# Switches.net
KiCad netlist of a schematic drawn in EAGLE
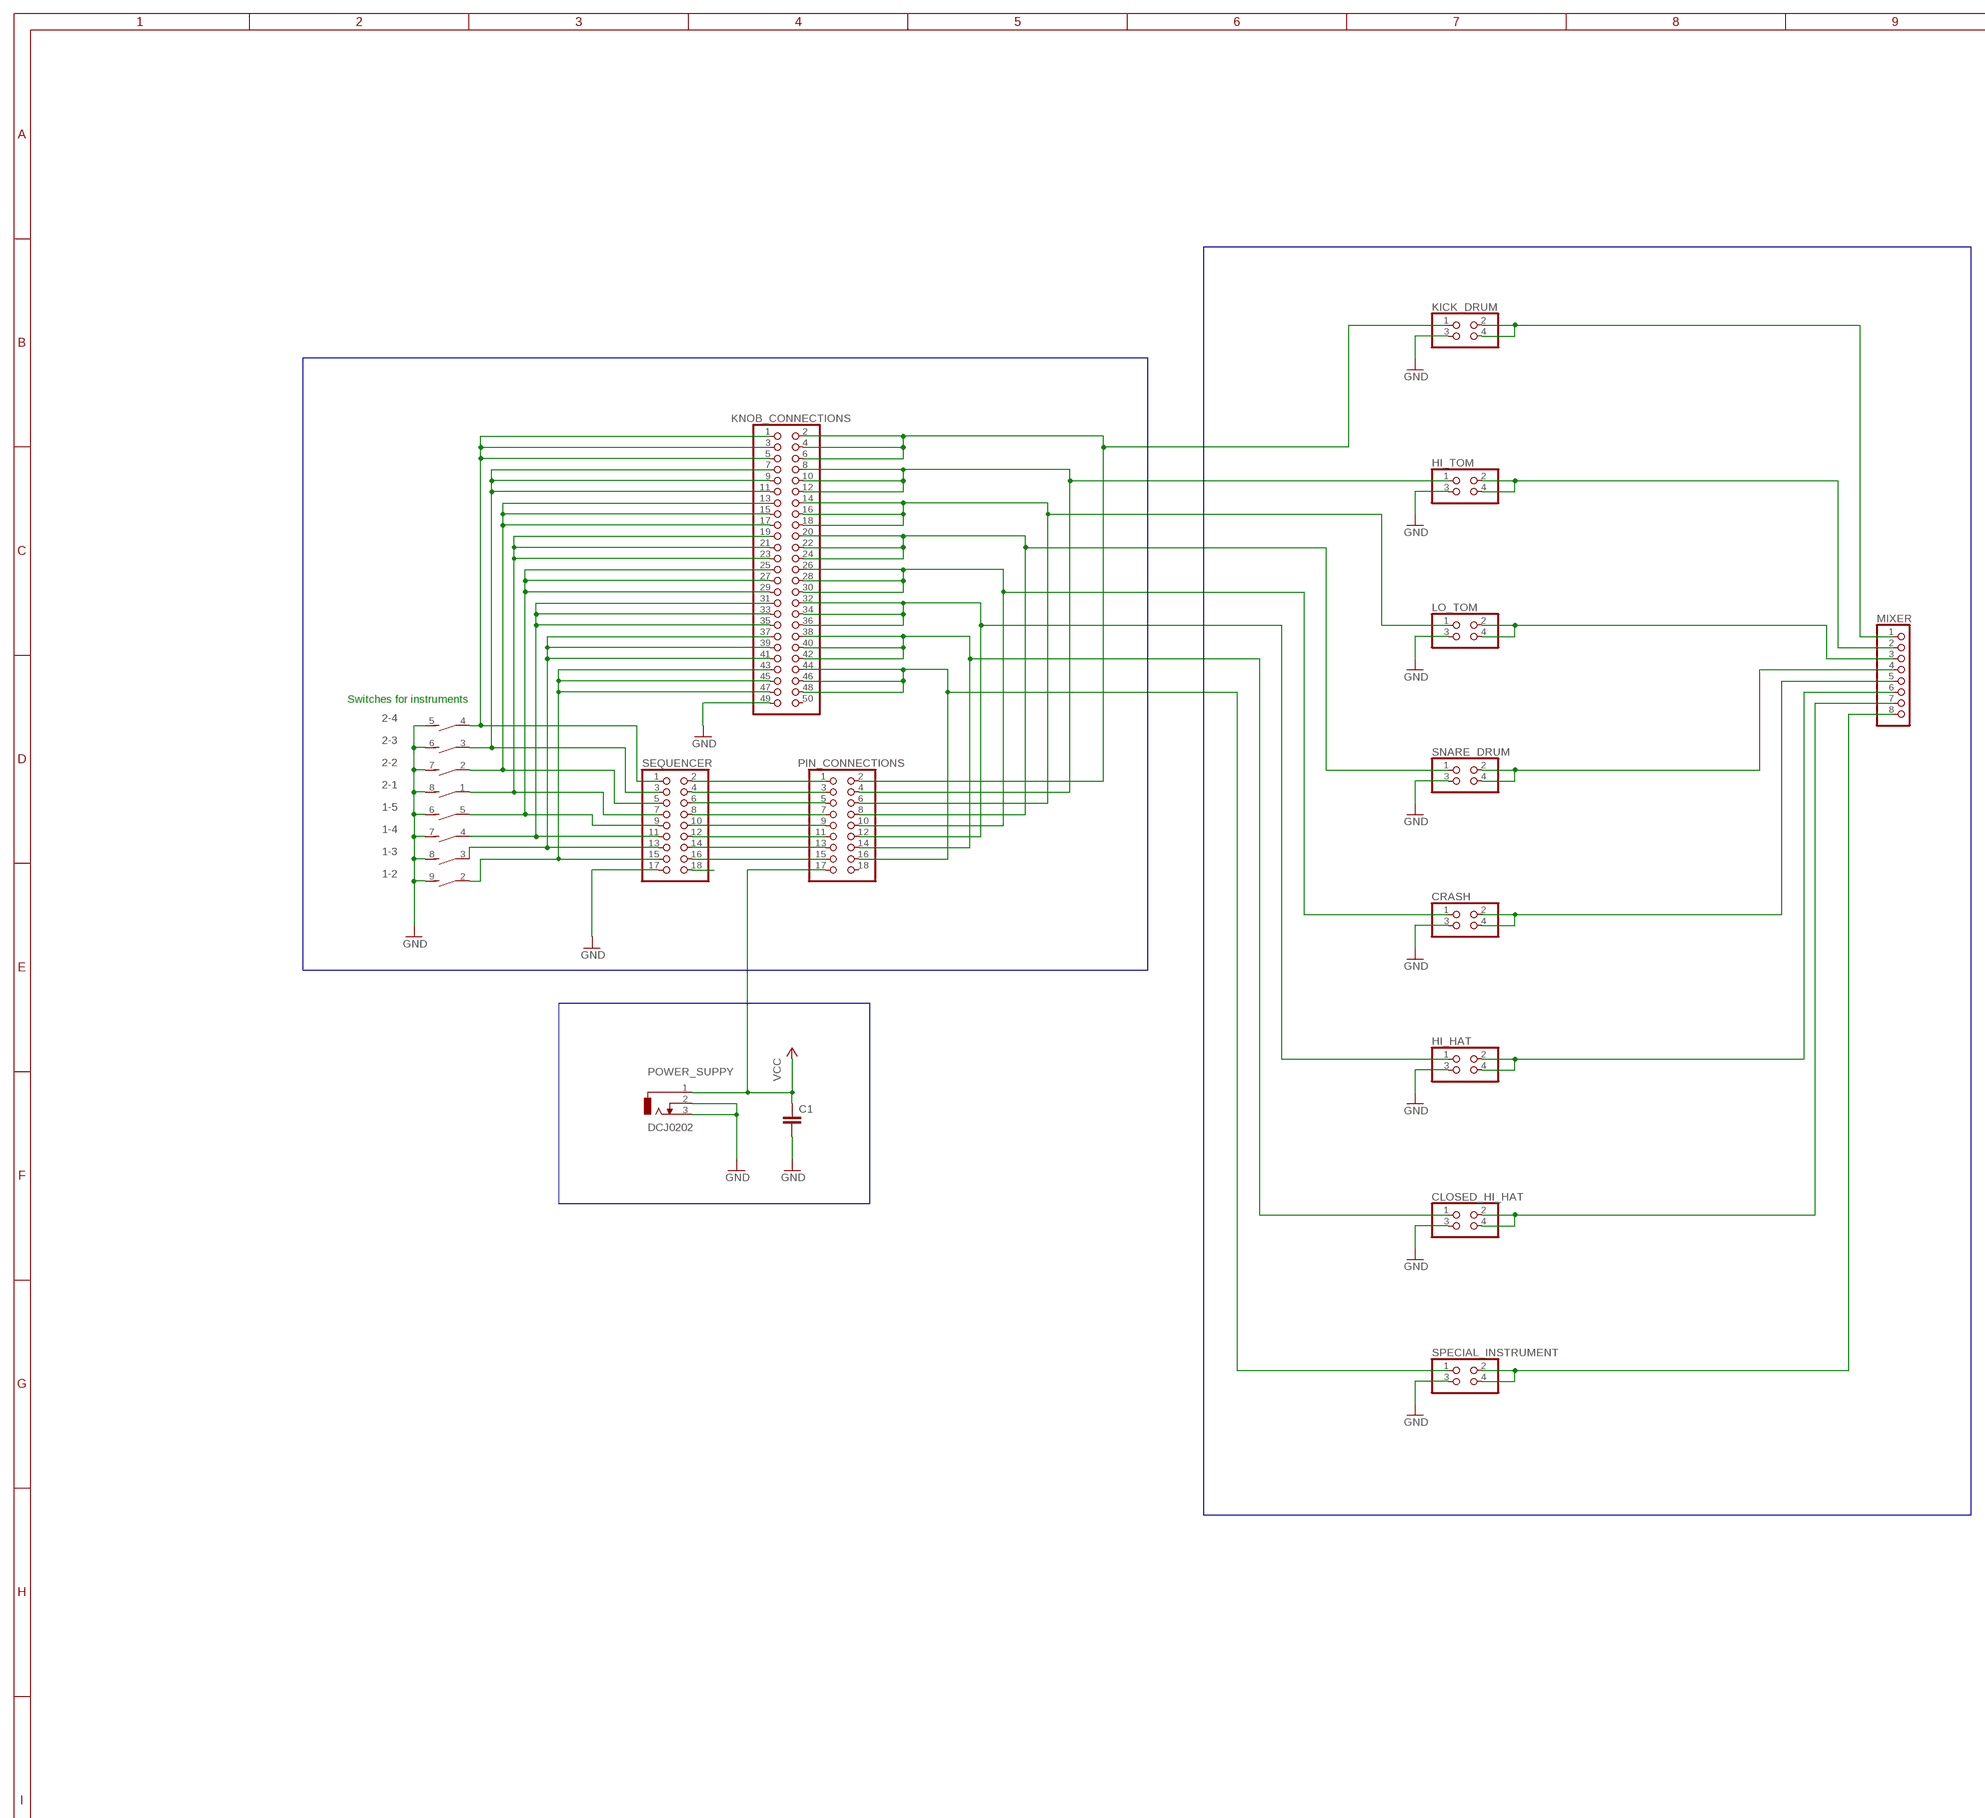
[diagram p0: schematic, sheet 1, part 1 of 2]
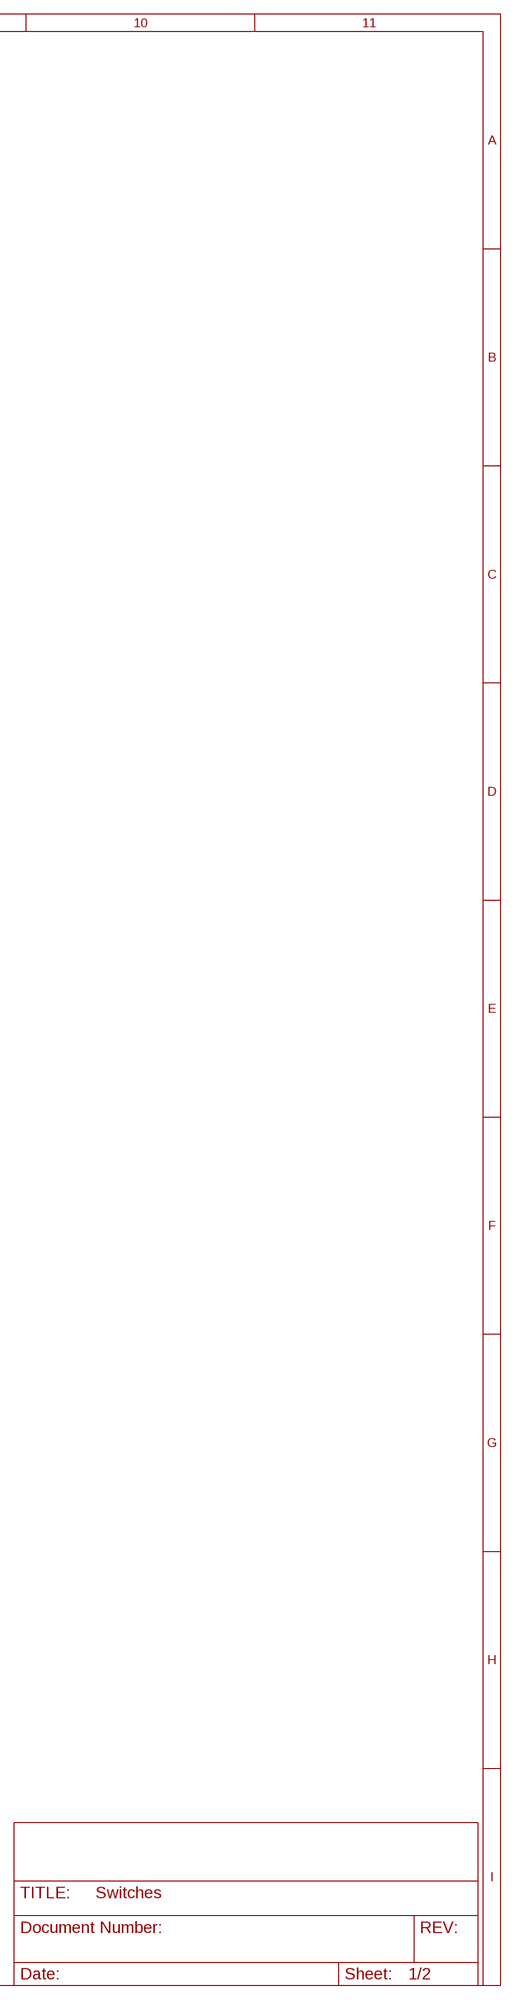
[diagram p1: schematic, sheet 1, part 2 of 2]
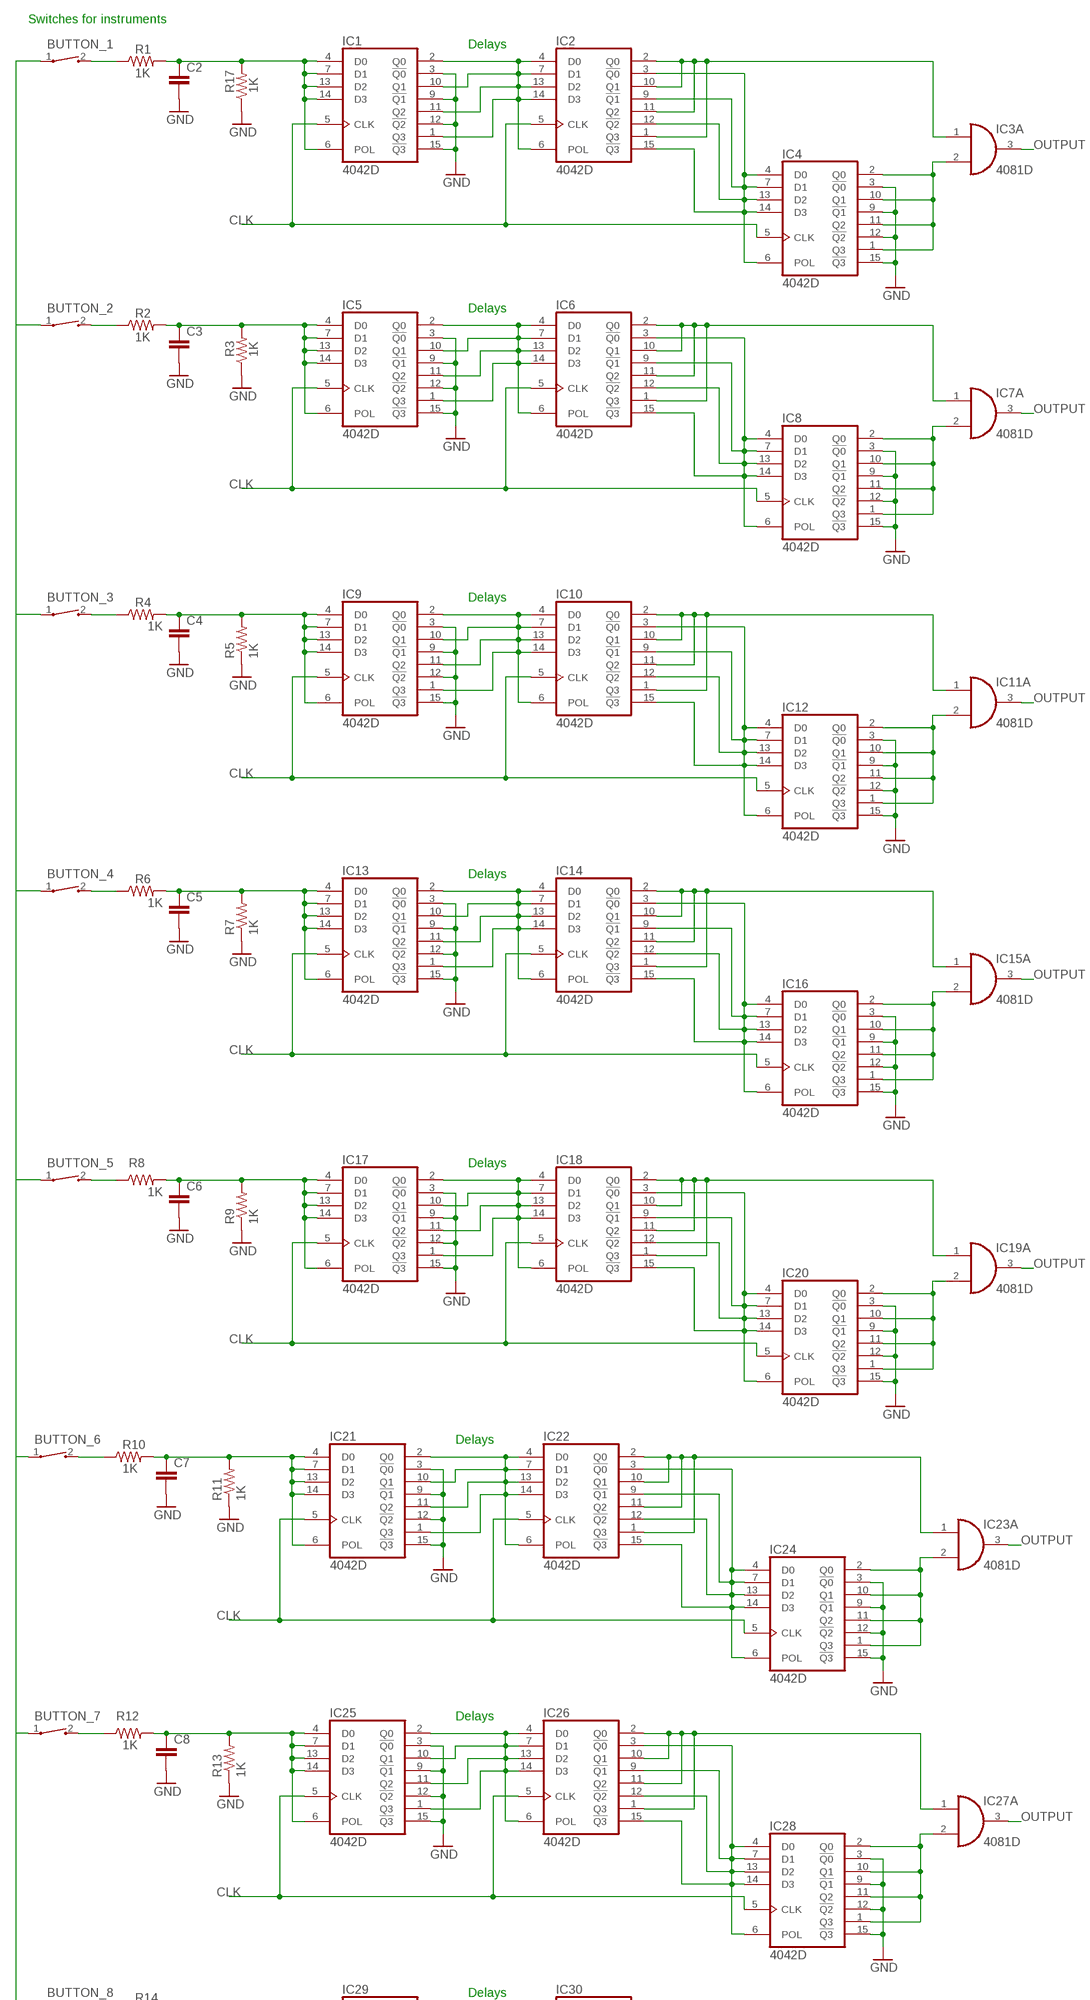
[diagram p2: schematic, sheet 2, part 1 of 3]
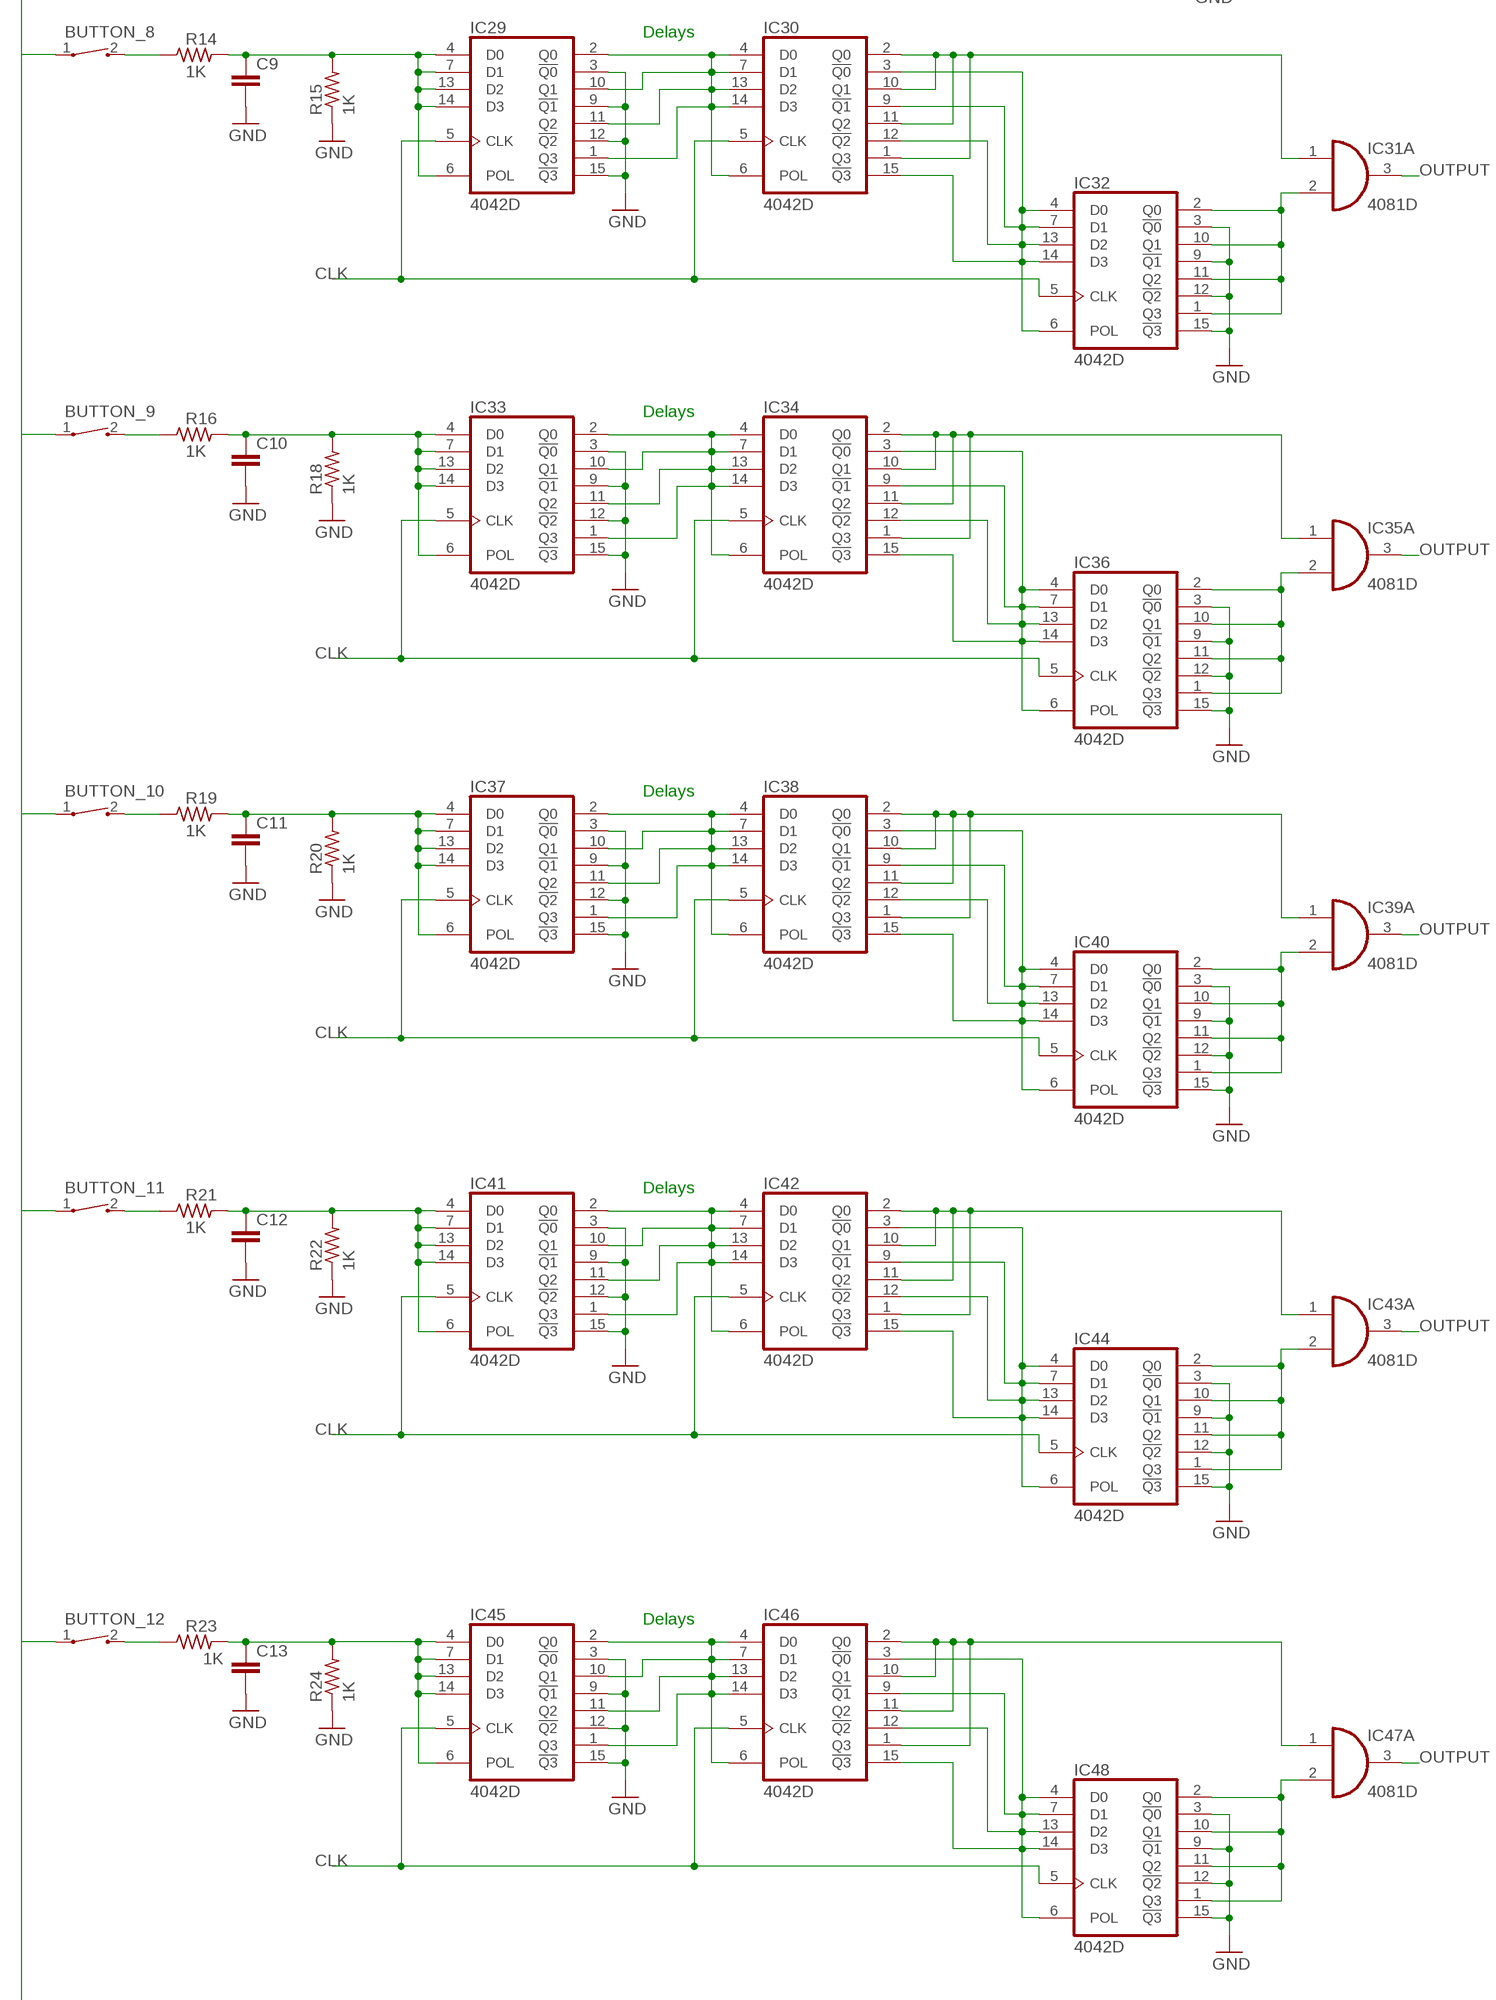
[diagram p3: schematic, sheet 2, part 2 of 3]
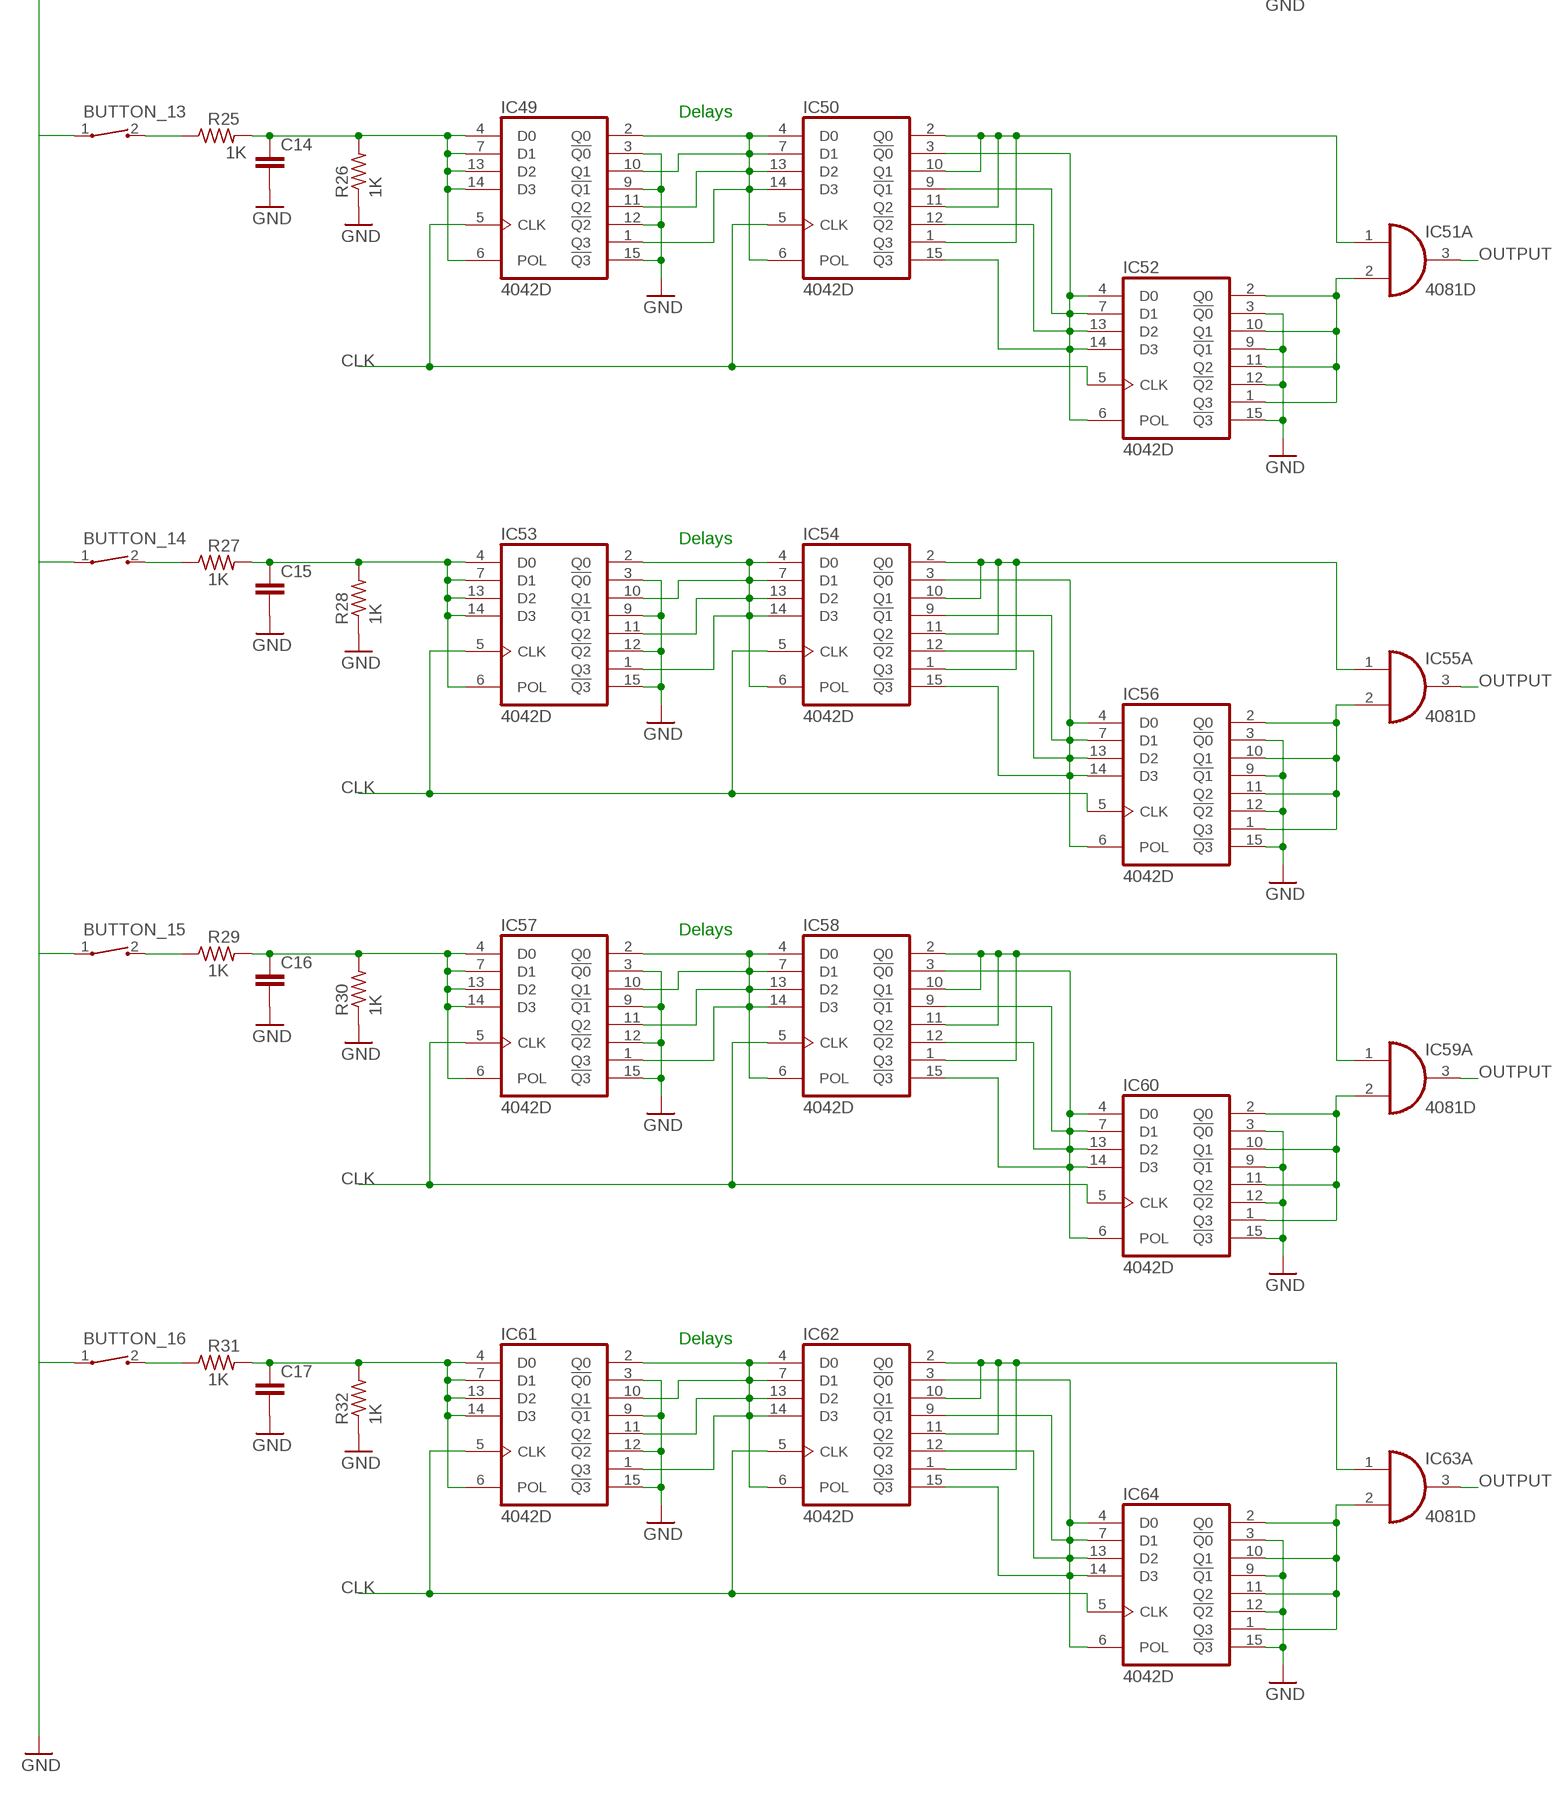
[diagram p4: schematic, sheet 2, part 3 of 3]

(export (version "E")
  (design (tool "Eeschema 10.0.6"))
  (components
    (comp (ref "1")
      (value "DS05E")
      (footprint "eagle-import:DS-05")
      (libsource (lib "eagle-import") (part "DS05E"))
    )
    (comp (ref "2")
      (value "DIP04S")
      (footprint "eagle-import:DIP04S")
      (libsource (lib "eagle-import") (part "DIP04S"))
    )
    (comp (ref "C1")
      (value "C2,5-3")
      (footprint "eagle-import:C2.5-3")
      (libsource (lib "eagle-import") (part "C2,5-3"))
    )
    (comp (ref "CLOSED_HI_HAT")
      (value "PINHD-2X2")
      (footprint "eagle-import:2X02")
      (libsource (lib "eagle-import") (part "PINHD-2X2"))
    )
    (comp (ref "CRASH")
      (value "PINHD-2X2")
      (footprint "eagle-import:2X02")
      (libsource (lib "eagle-import") (part "PINHD-2X2"))
    )
    (comp (ref "HI_HAT")
      (value "PINHD-2X2")
      (footprint "eagle-import:2X02")
      (libsource (lib "eagle-import") (part "PINHD-2X2"))
    )
    (comp (ref "HI_TOM")
      (value "PINHD-2X2")
      (footprint "eagle-import:2X02")
      (libsource (lib "eagle-import") (part "PINHD-2X2"))
    )
    (comp (ref "KICK_DRUM")
      (value "PINHD-2X2")
      (footprint "eagle-import:2X02")
      (libsource (lib "eagle-import") (part "PINHD-2X2"))
    )
    (comp (ref "KNOB_CONNECTIONS")
      (value "PINHD-2X25")
      (footprint "eagle-import:2X25")
      (libsource (lib "eagle-import") (part "PINHD-2X25"))
    )
    (comp (ref "LO_TOM")
      (value "PINHD-2X2")
      (footprint "eagle-import:2X02")
      (libsource (lib "eagle-import") (part "PINHD-2X2"))
    )
    (comp (ref "MIXER")
      (value "PINHD-1X8")
      (footprint "eagle-import:1X08")
      (libsource (lib "eagle-import") (part "PINHD-1X8"))
    )
    (comp (ref "PIN_CONNECTIONS")
      (value "PINHD-2X9")
      (footprint "eagle-import:2X09")
      (libsource (lib "eagle-import") (part "PINHD-2X9"))
    )
    (comp (ref "POWER_SUPPY")
      (value "DCJ0202")
      (footprint "eagle-import:DCJ0202")
      (libsource (lib "eagle-import") (part "DCJ0202"))
    )
    (comp (ref "SEQUENCER")
      (value "PINHD-2X9")
      (footprint "eagle-import:2X09")
      (libsource (lib "eagle-import") (part "PINHD-2X9"))
    )
    (comp (ref "SNARE_DRUM")
      (value "PINHD-2X2")
      (footprint "eagle-import:2X02")
      (libsource (lib "eagle-import") (part "PINHD-2X2"))
    )
    (comp (ref "SPECIAL_INSTRUMENT")
      (value "PINHD-2X2")
      (footprint "eagle-import:2X02")
      (libsource (lib "eagle-import") (part "PINHD-2X2"))
    )
    (comp (ref "BUTTON_1")
      (value "CT10-XXXX-A2")
      (footprint "eagle-import:CT10-XXXX-A2")
      (libsource (lib "eagle-import") (part "CT10-XXXX-A2"))
    )
    (comp (ref "BUTTON_2")
      (value "CT10-XXXX-A2")
      (footprint "eagle-import:CT10-XXXX-A2")
      (libsource (lib "eagle-import") (part "CT10-XXXX-A2"))
    )
    (comp (ref "BUTTON_3")
      (value "CT10-XXXX-A2")
      (footprint "eagle-import:CT10-XXXX-A2")
      (libsource (lib "eagle-import") (part "CT10-XXXX-A2"))
    )
    (comp (ref "BUTTON_4")
      (value "CT10-XXXX-A2")
      (footprint "eagle-import:CT10-XXXX-A2")
      (libsource (lib "eagle-import") (part "CT10-XXXX-A2"))
    )
    (comp (ref "BUTTON_5")
      (value "CT10-XXXX-A2")
      (footprint "eagle-import:CT10-XXXX-A2")
      (libsource (lib "eagle-import") (part "CT10-XXXX-A2"))
    )
    (comp (ref "BUTTON_6")
      (value "CT10-XXXX-A2")
      (footprint "eagle-import:CT10-XXXX-A2")
      (libsource (lib "eagle-import") (part "CT10-XXXX-A2"))
    )
    (comp (ref "BUTTON_7")
      (value "CT10-XXXX-A2")
      (footprint "eagle-import:CT10-XXXX-A2")
      (libsource (lib "eagle-import") (part "CT10-XXXX-A2"))
    )
    (comp (ref "BUTTON_8")
      (value "CT10-XXXX-A2")
      (footprint "eagle-import:CT10-XXXX-A2")
      (libsource (lib "eagle-import") (part "CT10-XXXX-A2"))
    )
    (comp (ref "BUTTON_9")
      (value "CT10-XXXX-A2")
      (footprint "eagle-import:CT10-XXXX-A2")
      (libsource (lib "eagle-import") (part "CT10-XXXX-A2"))
    )
    (comp (ref "BUTTON_10")
      (value "CT10-XXXX-A2")
      (footprint "eagle-import:CT10-XXXX-A2")
      (libsource (lib "eagle-import") (part "CT10-XXXX-A2"))
    )
    (comp (ref "BUTTON_11")
      (value "CT10-XXXX-A2")
      (footprint "eagle-import:CT10-XXXX-A2")
      (libsource (lib "eagle-import") (part "CT10-XXXX-A2"))
    )
    (comp (ref "BUTTON_12")
      (value "CT10-XXXX-A2")
      (footprint "eagle-import:CT10-XXXX-A2")
      (libsource (lib "eagle-import") (part "CT10-XXXX-A2"))
    )
    (comp (ref "BUTTON_13")
      (value "CT10-XXXX-A2")
      (footprint "eagle-import:CT10-XXXX-A2")
      (libsource (lib "eagle-import") (part "CT10-XXXX-A2"))
    )
    (comp (ref "BUTTON_14")
      (value "CT10-XXXX-A2")
      (footprint "eagle-import:CT10-XXXX-A2")
      (libsource (lib "eagle-import") (part "CT10-XXXX-A2"))
    )
    (comp (ref "BUTTON_15")
      (value "CT10-XXXX-A2")
      (footprint "eagle-import:CT10-XXXX-A2")
      (libsource (lib "eagle-import") (part "CT10-XXXX-A2"))
    )
    (comp (ref "BUTTON_16")
      (value "CT10-XXXX-A2")
      (footprint "eagle-import:CT10-XXXX-A2")
      (libsource (lib "eagle-import") (part "CT10-XXXX-A2"))
    )
    (comp (ref "C2")
      (value "C5/3")
      (footprint "eagle-import:C5B3")
      (libsource (lib "eagle-import") (part "C5/3"))
    )
    (comp (ref "C3")
      (value "C5/3")
      (footprint "eagle-import:C5B3")
      (libsource (lib "eagle-import") (part "C5/3"))
    )
    (comp (ref "C4")
      (value "C5/3")
      (footprint "eagle-import:C5B3")
      (libsource (lib "eagle-import") (part "C5/3"))
    )
    (comp (ref "C5")
      (value "C5/3")
      (footprint "eagle-import:C5B3")
      (libsource (lib "eagle-import") (part "C5/3"))
    )
    (comp (ref "C6")
      (value "C5/3")
      (footprint "eagle-import:C5B3")
      (libsource (lib "eagle-import") (part "C5/3"))
    )
    (comp (ref "C7")
      (value "C5/3")
      (footprint "eagle-import:C5B3")
      (libsource (lib "eagle-import") (part "C5/3"))
    )
    (comp (ref "C8")
      (value "C5/3")
      (footprint "eagle-import:C5B3")
      (libsource (lib "eagle-import") (part "C5/3"))
    )
    (comp (ref "C9")
      (value "C5/3")
      (footprint "eagle-import:C5B3")
      (libsource (lib "eagle-import") (part "C5/3"))
    )
    (comp (ref "C10")
      (value "C5/3")
      (footprint "eagle-import:C5B3")
      (libsource (lib "eagle-import") (part "C5/3"))
    )
    (comp (ref "C11")
      (value "C5/3")
      (footprint "eagle-import:C5B3")
      (libsource (lib "eagle-import") (part "C5/3"))
    )
    (comp (ref "C12")
      (value "C5/3")
      (footprint "eagle-import:C5B3")
      (libsource (lib "eagle-import") (part "C5/3"))
    )
    (comp (ref "C13")
      (value "C5/3")
      (footprint "eagle-import:C5B3")
      (libsource (lib "eagle-import") (part "C5/3"))
    )
    (comp (ref "C14")
      (value "C5/3")
      (footprint "eagle-import:C5B3")
      (libsource (lib "eagle-import") (part "C5/3"))
    )
    (comp (ref "C15")
      (value "C5/3")
      (footprint "eagle-import:C5B3")
      (libsource (lib "eagle-import") (part "C5/3"))
    )
    (comp (ref "C16")
      (value "C5/3")
      (footprint "eagle-import:C5B3")
      (libsource (lib "eagle-import") (part "C5/3"))
    )
    (comp (ref "C17")
      (value "C5/3")
      (footprint "eagle-import:C5B3")
      (libsource (lib "eagle-import") (part "C5/3"))
    )
    (comp (ref "IC1")
      (value "4042D")
      (footprint "eagle-import:SO16")
      (libsource (lib "eagle-import") (part "4042D"))
    )
    (comp (ref "IC2")
      (value "4042D")
      (footprint "eagle-import:SO16")
      (libsource (lib "eagle-import") (part "4042D"))
    )
    (comp (ref "IC3")
      (value "4081D")
      (footprint "eagle-import:SO14")
      (libsource (lib "eagle-import") (part "4081D"))
    )
    (comp (ref "IC4")
      (value "4042D")
      (footprint "eagle-import:SO16")
      (libsource (lib "eagle-import") (part "4042D"))
    )
    (comp (ref "IC5")
      (value "4042D")
      (footprint "eagle-import:SO16")
      (libsource (lib "eagle-import") (part "4042D"))
    )
    (comp (ref "IC6")
      (value "4042D")
      (footprint "eagle-import:SO16")
      (libsource (lib "eagle-import") (part "4042D"))
    )
    (comp (ref "IC7")
      (value "4081D")
      (footprint "eagle-import:SO14")
      (libsource (lib "eagle-import") (part "4081D"))
    )
    (comp (ref "IC8")
      (value "4042D")
      (footprint "eagle-import:SO16")
      (libsource (lib "eagle-import") (part "4042D"))
    )
    (comp (ref "IC9")
      (value "4042D")
      (footprint "eagle-import:SO16")
      (libsource (lib "eagle-import") (part "4042D"))
    )
    (comp (ref "IC10")
      (value "4042D")
      (footprint "eagle-import:SO16")
      (libsource (lib "eagle-import") (part "4042D"))
    )
    (comp (ref "IC11")
      (value "4081D")
      (footprint "eagle-import:SO14")
      (libsource (lib "eagle-import") (part "4081D"))
    )
    (comp (ref "IC12")
      (value "4042D")
      (footprint "eagle-import:SO16")
      (libsource (lib "eagle-import") (part "4042D"))
    )
    (comp (ref "IC13")
      (value "4042D")
      (footprint "eagle-import:SO16")
      (libsource (lib "eagle-import") (part "4042D"))
    )
    (comp (ref "IC14")
      (value "4042D")
      (footprint "eagle-import:SO16")
      (libsource (lib "eagle-import") (part "4042D"))
    )
    (comp (ref "IC15")
      (value "4081D")
      (footprint "eagle-import:SO14")
      (libsource (lib "eagle-import") (part "4081D"))
    )
    (comp (ref "IC16")
      (value "4042D")
      (footprint "eagle-import:SO16")
      (libsource (lib "eagle-import") (part "4042D"))
    )
    (comp (ref "IC17")
      (value "4042D")
      (footprint "eagle-import:SO16")
      (libsource (lib "eagle-import") (part "4042D"))
    )
    (comp (ref "IC18")
      (value "4042D")
      (footprint "eagle-import:SO16")
      (libsource (lib "eagle-import") (part "4042D"))
    )
    (comp (ref "IC19")
      (value "4081D")
      (footprint "eagle-import:SO14")
      (libsource (lib "eagle-import") (part "4081D"))
    )
    (comp (ref "IC20")
      (value "4042D")
      (footprint "eagle-import:SO16")
      (libsource (lib "eagle-import") (part "4042D"))
    )
    (comp (ref "IC21")
      (value "4042D")
      (footprint "eagle-import:SO16")
      (libsource (lib "eagle-import") (part "4042D"))
    )
    (comp (ref "IC22")
      (value "4042D")
      (footprint "eagle-import:SO16")
      (libsource (lib "eagle-import") (part "4042D"))
    )
    (comp (ref "IC23")
      (value "4081D")
      (footprint "eagle-import:SO14")
      (libsource (lib "eagle-import") (part "4081D"))
    )
    (comp (ref "IC24")
      (value "4042D")
      (footprint "eagle-import:SO16")
      (libsource (lib "eagle-import") (part "4042D"))
    )
    (comp (ref "IC25")
      (value "4042D")
      (footprint "eagle-import:SO16")
      (libsource (lib "eagle-import") (part "4042D"))
    )
    (comp (ref "IC26")
      (value "4042D")
      (footprint "eagle-import:SO16")
      (libsource (lib "eagle-import") (part "4042D"))
    )
    (comp (ref "IC27")
      (value "4081D")
      (footprint "eagle-import:SO14")
      (libsource (lib "eagle-import") (part "4081D"))
    )
    (comp (ref "IC28")
      (value "4042D")
      (footprint "eagle-import:SO16")
      (libsource (lib "eagle-import") (part "4042D"))
    )
    (comp (ref "IC29")
      (value "4042D")
      (footprint "eagle-import:SO16")
      (libsource (lib "eagle-import") (part "4042D"))
    )
    (comp (ref "IC30")
      (value "4042D")
      (footprint "eagle-import:SO16")
      (libsource (lib "eagle-import") (part "4042D"))
    )
    (comp (ref "IC31")
      (value "4081D")
      (footprint "eagle-import:SO14")
      (libsource (lib "eagle-import") (part "4081D"))
    )
    (comp (ref "IC32")
      (value "4042D")
      (footprint "eagle-import:SO16")
      (libsource (lib "eagle-import") (part "4042D"))
    )
    (comp (ref "IC33")
      (value "4042D")
      (footprint "eagle-import:SO16")
      (libsource (lib "eagle-import") (part "4042D"))
    )
    (comp (ref "IC34")
      (value "4042D")
      (footprint "eagle-import:SO16")
      (libsource (lib "eagle-import") (part "4042D"))
    )
    (comp (ref "IC35")
      (value "4081D")
      (footprint "eagle-import:SO14")
      (libsource (lib "eagle-import") (part "4081D"))
    )
    (comp (ref "IC36")
      (value "4042D")
      (footprint "eagle-import:SO16")
      (libsource (lib "eagle-import") (part "4042D"))
    )
    (comp (ref "IC37")
      (value "4042D")
      (footprint "eagle-import:SO16")
      (libsource (lib "eagle-import") (part "4042D"))
    )
    (comp (ref "IC38")
      (value "4042D")
      (footprint "eagle-import:SO16")
      (libsource (lib "eagle-import") (part "4042D"))
    )
    (comp (ref "IC39")
      (value "4081D")
      (footprint "eagle-import:SO14")
      (libsource (lib "eagle-import") (part "4081D"))
    )
    (comp (ref "IC40")
      (value "4042D")
      (footprint "eagle-import:SO16")
      (libsource (lib "eagle-import") (part "4042D"))
    )
    (comp (ref "IC41")
      (value "4042D")
      (footprint "eagle-import:SO16")
      (libsource (lib "eagle-import") (part "4042D"))
    )
    (comp (ref "IC42")
      (value "4042D")
      (footprint "eagle-import:SO16")
      (libsource (lib "eagle-import") (part "4042D"))
    )
    (comp (ref "IC43")
      (value "4081D")
      (footprint "eagle-import:SO14")
      (libsource (lib "eagle-import") (part "4081D"))
    )
    (comp (ref "IC44")
      (value "4042D")
      (footprint "eagle-import:SO16")
      (libsource (lib "eagle-import") (part "4042D"))
    )
    (comp (ref "IC45")
      (value "4042D")
      (footprint "eagle-import:SO16")
      (libsource (lib "eagle-import") (part "4042D"))
    )
    (comp (ref "IC46")
      (value "4042D")
      (footprint "eagle-import:SO16")
      (libsource (lib "eagle-import") (part "4042D"))
    )
    (comp (ref "IC47")
      (value "4081D")
      (footprint "eagle-import:SO14")
      (libsource (lib "eagle-import") (part "4081D"))
    )
    (comp (ref "IC48")
      (value "4042D")
      (footprint "eagle-import:SO16")
      (libsource (lib "eagle-import") (part "4042D"))
    )
    (comp (ref "IC49")
      (value "4042D")
      (footprint "eagle-import:SO16")
      (libsource (lib "eagle-import") (part "4042D"))
    )
    (comp (ref "IC50")
      (value "4042D")
      (footprint "eagle-import:SO16")
      (libsource (lib "eagle-import") (part "4042D"))
    )
    (comp (ref "IC51")
      (value "4081D")
      (footprint "eagle-import:SO14")
      (libsource (lib "eagle-import") (part "4081D"))
    )
    (comp (ref "IC52")
      (value "4042D")
      (footprint "eagle-import:SO16")
      (libsource (lib "eagle-import") (part "4042D"))
    )
    (comp (ref "IC53")
      (value "4042D")
      (footprint "eagle-import:SO16")
      (libsource (lib "eagle-import") (part "4042D"))
    )
    (comp (ref "IC54")
      (value "4042D")
      (footprint "eagle-import:SO16")
      (libsource (lib "eagle-import") (part "4042D"))
    )
    (comp (ref "IC55")
      (value "4081D")
      (footprint "eagle-import:SO14")
      (libsource (lib "eagle-import") (part "4081D"))
    )
    (comp (ref "IC56")
      (value "4042D")
      (footprint "eagle-import:SO16")
      (libsource (lib "eagle-import") (part "4042D"))
    )
    (comp (ref "IC57")
      (value "4042D")
      (footprint "eagle-import:SO16")
      (libsource (lib "eagle-import") (part "4042D"))
    )
    (comp (ref "IC58")
      (value "4042D")
      (footprint "eagle-import:SO16")
      (libsource (lib "eagle-import") (part "4042D"))
    )
    (comp (ref "IC59")
      (value "4081D")
      (footprint "eagle-import:SO14")
      (libsource (lib "eagle-import") (part "4081D"))
    )
    (comp (ref "IC60")
      (value "4042D")
      (footprint "eagle-import:SO16")
      (libsource (lib "eagle-import") (part "4042D"))
    )
    (comp (ref "IC61")
      (value "4042D")
      (footprint "eagle-import:SO16")
      (libsource (lib "eagle-import") (part "4042D"))
    )
    (comp (ref "IC62")
      (value "4042D")
      (footprint "eagle-import:SO16")
      (libsource (lib "eagle-import") (part "4042D"))
    )
    (comp (ref "IC63")
      (value "4081D")
      (footprint "eagle-import:SO14")
      (libsource (lib "eagle-import") (part "4081D"))
    )
    (comp (ref "IC64")
      (value "4042D")
      (footprint "eagle-import:SO16")
      (libsource (lib "eagle-import") (part "4042D"))
    )
    (comp (ref "R1")
      (value "1K")
      (footprint "eagle-import:0204_7")
      (libsource (lib "eagle-import") (part "R-US_0204/7"))
    )
    (comp (ref "R2")
      (value "1K")
      (footprint "eagle-import:0204_7")
      (libsource (lib "eagle-import") (part "R-US_0204/7"))
    )
    (comp (ref "R3")
      (value "1K")
      (footprint "eagle-import:0204_7")
      (libsource (lib "eagle-import") (part "R-US_0204/7"))
    )
    (comp (ref "R4")
      (value "1K")
      (footprint "eagle-import:0204_7")
      (libsource (lib "eagle-import") (part "R-US_0204/7"))
    )
    (comp (ref "R5")
      (value "1K")
      (footprint "eagle-import:0204_7")
      (libsource (lib "eagle-import") (part "R-US_0204/7"))
    )
    (comp (ref "R6")
      (value "1K")
      (footprint "eagle-import:0204_7")
      (libsource (lib "eagle-import") (part "R-US_0204/7"))
    )
    (comp (ref "R7")
      (value "1K")
      (footprint "eagle-import:0204_7")
      (libsource (lib "eagle-import") (part "R-US_0204/7"))
    )
    (comp (ref "R8")
      (value "1K")
      (footprint "eagle-import:0204_7")
      (libsource (lib "eagle-import") (part "R-US_0204/7"))
    )
    (comp (ref "R9")
      (value "1K")
      (footprint "eagle-import:0204_7")
      (libsource (lib "eagle-import") (part "R-US_0204/7"))
    )
    (comp (ref "R10")
      (value "1K")
      (footprint "eagle-import:0204_7")
      (libsource (lib "eagle-import") (part "R-US_0204/7"))
    )
    (comp (ref "R11")
      (value "1K")
      (footprint "eagle-import:0204_7")
      (libsource (lib "eagle-import") (part "R-US_0204/7"))
    )
    (comp (ref "R12")
      (value "1K")
      (footprint "eagle-import:0204_7")
      (libsource (lib "eagle-import") (part "R-US_0204/7"))
    )
    (comp (ref "R13")
      (value "1K")
      (footprint "eagle-import:0204_7")
      (libsource (lib "eagle-import") (part "R-US_0204/7"))
    )
    (comp (ref "R14")
      (value "1K")
      (footprint "eagle-import:0204_7")
      (libsource (lib "eagle-import") (part "R-US_0204/7"))
    )
    (comp (ref "R15")
      (value "1K")
      (footprint "eagle-import:0204_7")
      (libsource (lib "eagle-import") (part "R-US_0204/7"))
    )
    (comp (ref "R16")
      (value "1K")
      (footprint "eagle-import:0204_7")
      (libsource (lib "eagle-import") (part "R-US_0204/7"))
    )
    (comp (ref "R17")
      (value "1K")
      (footprint "eagle-import:0204_7")
      (libsource (lib "eagle-import") (part "R-US_0204/7"))
    )
    (comp (ref "R18")
      (value "1K")
      (footprint "eagle-import:0204_7")
      (libsource (lib "eagle-import") (part "R-US_0204/7"))
    )
    (comp (ref "R19")
      (value "1K")
      (footprint "eagle-import:0204_7")
      (libsource (lib "eagle-import") (part "R-US_0204/7"))
    )
    (comp (ref "R20")
      (value "1K")
      (footprint "eagle-import:0204_7")
      (libsource (lib "eagle-import") (part "R-US_0204/7"))
    )
    (comp (ref "R21")
      (value "1K")
      (footprint "eagle-import:0204_7")
      (libsource (lib "eagle-import") (part "R-US_0204/7"))
    )
    (comp (ref "R22")
      (value "1K")
      (footprint "eagle-import:0204_7")
      (libsource (lib "eagle-import") (part "R-US_0204/7"))
    )
    (comp (ref "R23")
      (value "1K")
      (footprint "eagle-import:0204_7")
      (libsource (lib "eagle-import") (part "R-US_0204/7"))
    )
    (comp (ref "R24")
      (value "1K")
      (footprint "eagle-import:0204_7")
      (libsource (lib "eagle-import") (part "R-US_0204/7"))
    )
    (comp (ref "R25")
      (value "1K")
      (footprint "eagle-import:0204_7")
      (libsource (lib "eagle-import") (part "R-US_0204/7"))
    )
    (comp (ref "R26")
      (value "1K")
      (footprint "eagle-import:0204_7")
      (libsource (lib "eagle-import") (part "R-US_0204/7"))
    )
    (comp (ref "R27")
      (value "1K")
      (footprint "eagle-import:0204_7")
      (libsource (lib "eagle-import") (part "R-US_0204/7"))
    )
    (comp (ref "R28")
      (value "1K")
      (footprint "eagle-import:0204_7")
      (libsource (lib "eagle-import") (part "R-US_0204/7"))
    )
    (comp (ref "R29")
      (value "1K")
      (footprint "eagle-import:0204_7")
      (libsource (lib "eagle-import") (part "R-US_0204/7"))
    )
    (comp (ref "R30")
      (value "1K")
      (footprint "eagle-import:0204_7")
      (libsource (lib "eagle-import") (part "R-US_0204/7"))
    )
    (comp (ref "R31")
      (value "1K")
      (footprint "eagle-import:0204_7")
      (libsource (lib "eagle-import") (part "R-US_0204/7"))
    )
    (comp (ref "R32")
      (value "1K")
      (footprint "eagle-import:0204_7")
      (libsource (lib "eagle-import") (part "R-US_0204/7"))
    )
  )
  (nets
    (net (code "1") (name "CLK") (class "Default")
      (node (ref "IC1") (pin "5") (pinfunction "CLK_5") (pintype "input"))
      (node (ref "IC10") (pin "5") (pinfunction "CLK_5") (pintype "input"))
      (node (ref "IC12") (pin "5") (pinfunction "CLK_5") (pintype "input"))
      (node (ref "IC13") (pin "5") (pinfunction "CLK_5") (pintype "input"))
      (node (ref "IC14") (pin "5") (pinfunction "CLK_5") (pintype "input"))
      (node (ref "IC16") (pin "5") (pinfunction "CLK_5") (pintype "input"))
      (node (ref "IC17") (pin "5") (pinfunction "CLK_5") (pintype "input"))
      (node (ref "IC18") (pin "5") (pinfunction "CLK_5") (pintype "input"))
      (node (ref "IC2") (pin "5") (pinfunction "CLK_5") (pintype "input"))
      (node (ref "IC20") (pin "5") (pinfunction "CLK_5") (pintype "input"))
      (node (ref "IC21") (pin "5") (pinfunction "CLK_5") (pintype "input"))
      (node (ref "IC22") (pin "5") (pinfunction "CLK_5") (pintype "input"))
      (node (ref "IC24") (pin "5") (pinfunction "CLK_5") (pintype "input"))
      (node (ref "IC25") (pin "5") (pinfunction "CLK_5") (pintype "input"))
      (node (ref "IC26") (pin "5") (pinfunction "CLK_5") (pintype "input"))
      (node (ref "IC28") (pin "5") (pinfunction "CLK_5") (pintype "input"))
      (node (ref "IC29") (pin "5") (pinfunction "CLK_5") (pintype "input"))
      (node (ref "IC30") (pin "5") (pinfunction "CLK_5") (pintype "input"))
      (node (ref "IC32") (pin "5") (pinfunction "CLK_5") (pintype "input"))
      (node (ref "IC33") (pin "5") (pinfunction "CLK_5") (pintype "input"))
      (node (ref "IC34") (pin "5") (pinfunction "CLK_5") (pintype "input"))
      (node (ref "IC36") (pin "5") (pinfunction "CLK_5") (pintype "input"))
      (node (ref "IC37") (pin "5") (pinfunction "CLK_5") (pintype "input"))
      (node (ref "IC38") (pin "5") (pinfunction "CLK_5") (pintype "input"))
      (node (ref "IC4") (pin "5") (pinfunction "CLK_5") (pintype "input"))
      (node (ref "IC40") (pin "5") (pinfunction "CLK_5") (pintype "input"))
      (node (ref "IC41") (pin "5") (pinfunction "CLK_5") (pintype "input"))
      (node (ref "IC42") (pin "5") (pinfunction "CLK_5") (pintype "input"))
      (node (ref "IC44") (pin "5") (pinfunction "CLK_5") (pintype "input"))
      (node (ref "IC45") (pin "5") (pinfunction "CLK_5") (pintype "input"))
      (node (ref "IC46") (pin "5") (pinfunction "CLK_5") (pintype "input"))
      (node (ref "IC48") (pin "5") (pinfunction "CLK_5") (pintype "input"))
      (node (ref "IC49") (pin "5") (pinfunction "CLK_5") (pintype "input"))
      (node (ref "IC5") (pin "5") (pinfunction "CLK_5") (pintype "input"))
      (node (ref "IC50") (pin "5") (pinfunction "CLK_5") (pintype "input"))
      (node (ref "IC52") (pin "5") (pinfunction "CLK_5") (pintype "input"))
      (node (ref "IC53") (pin "5") (pinfunction "CLK_5") (pintype "input"))
      (node (ref "IC54") (pin "5") (pinfunction "CLK_5") (pintype "input"))
      (node (ref "IC56") (pin "5") (pinfunction "CLK_5") (pintype "input"))
      (node (ref "IC57") (pin "5") (pinfunction "CLK_5") (pintype "input"))
      (node (ref "IC58") (pin "5") (pinfunction "CLK_5") (pintype "input"))
      (node (ref "IC6") (pin "5") (pinfunction "CLK_5") (pintype "input"))
      (node (ref "IC60") (pin "5") (pinfunction "CLK_5") (pintype "input"))
      (node (ref "IC61") (pin "5") (pinfunction "CLK_5") (pintype "input"))
      (node (ref "IC62") (pin "5") (pinfunction "CLK_5") (pintype "input"))
      (node (ref "IC64") (pin "5") (pinfunction "CLK_5") (pintype "input"))
      (node (ref "IC8") (pin "5") (pinfunction "CLK_5") (pintype "input"))
      (node (ref "IC9") (pin "5") (pinfunction "CLK_5") (pintype "input"))
    )
    (net (code "2") (name "GND") (class "Default")
      (node (ref "1") (pin "6") (pinfunction "2_6") (pintype "passive"))
      (node (ref "1") (pin "7") (pinfunction "2_7") (pintype "passive"))
      (node (ref "1") (pin "8") (pinfunction "2_8") (pintype "passive"))
      (node (ref "1") (pin "9") (pinfunction "2_9") (pintype "passive"))
      (node (ref "2") (pin "5") (pinfunction "2_5") (pintype "passive"))
      (node (ref "2") (pin "6") (pinfunction "2_6") (pintype "passive"))
      (node (ref "2") (pin "7") (pinfunction "2_7") (pintype "passive"))
      (node (ref "2") (pin "8") (pinfunction "2_8") (pintype "passive"))
      (node (ref "BUTTON_1") (pin "1") (pinfunction "1_1") (pintype "passive"))
      (node (ref "C1") (pin "2") (pinfunction "2_2") (pintype "passive"))
      (node (ref "C10") (pin "2") (pinfunction "2_2") (pintype "passive"))
      (node (ref "C11") (pin "2") (pinfunction "2_2") (pintype "passive"))
      (node (ref "C12") (pin "2") (pinfunction "2_2") (pintype "passive"))
      (node (ref "C13") (pin "2") (pinfunction "2_2") (pintype "passive"))
      (node (ref "C14") (pin "2") (pinfunction "2_2") (pintype "passive"))
      (node (ref "C15") (pin "2") (pinfunction "2_2") (pintype "passive"))
      (node (ref "C16") (pin "2") (pinfunction "2_2") (pintype "passive"))
      (node (ref "C17") (pin "2") (pinfunction "2_2") (pintype "passive"))
      (node (ref "C2") (pin "2") (pinfunction "2_2") (pintype "passive"))
      (node (ref "C3") (pin "2") (pinfunction "2_2") (pintype "passive"))
      (node (ref "C4") (pin "2") (pinfunction "2_2") (pintype "passive"))
      (node (ref "C5") (pin "2") (pinfunction "2_2") (pintype "passive"))
      (node (ref "C6") (pin "2") (pinfunction "2_2") (pintype "passive"))
      (node (ref "C7") (pin "2") (pinfunction "2_2") (pintype "passive"))
      (node (ref "C8") (pin "2") (pinfunction "2_2") (pintype "passive"))
      (node (ref "C9") (pin "2") (pinfunction "2_2") (pintype "passive"))
      (node (ref "CLOSED_HI_HAT") (pin "3") (pinfunction "3_3") (pintype "passive"))
      (node (ref "CRASH") (pin "3") (pinfunction "3_3") (pintype "passive"))
      (node (ref "HI_HAT") (pin "3") (pinfunction "3_3") (pintype "passive"))
      (node (ref "HI_TOM") (pin "3") (pinfunction "3_3") (pintype "passive"))
      (node (ref "IC1") (pin "12") (pinfunction "~{Q2}_12") (pintype "output"))
      (node (ref "IC1") (pin "15") (pinfunction "~{Q3}_15") (pintype "output"))
      (node (ref "IC1") (pin "3") (pinfunction "~{Q0}_3") (pintype "output"))
      (node (ref "IC1") (pin "9") (pinfunction "~{Q1}_9") (pintype "output"))
      (node (ref "IC12") (pin "12") (pinfunction "~{Q2}_12") (pintype "output"))
      (node (ref "IC12") (pin "15") (pinfunction "~{Q3}_15") (pintype "output"))
      (node (ref "IC12") (pin "3") (pinfunction "~{Q0}_3") (pintype "output"))
      (node (ref "IC12") (pin "9") (pinfunction "~{Q1}_9") (pintype "output"))
      (node (ref "IC13") (pin "12") (pinfunction "~{Q2}_12") (pintype "output"))
      (node (ref "IC13") (pin "15") (pinfunction "~{Q3}_15") (pintype "output"))
      (node (ref "IC13") (pin "3") (pinfunction "~{Q0}_3") (pintype "output"))
      (node (ref "IC13") (pin "9") (pinfunction "~{Q1}_9") (pintype "output"))
      (node (ref "IC16") (pin "12") (pinfunction "~{Q2}_12") (pintype "output"))
      (node (ref "IC16") (pin "15") (pinfunction "~{Q3}_15") (pintype "output"))
      (node (ref "IC16") (pin "3") (pinfunction "~{Q0}_3") (pintype "output"))
      (node (ref "IC16") (pin "9") (pinfunction "~{Q1}_9") (pintype "output"))
      (node (ref "IC17") (pin "12") (pinfunction "~{Q2}_12") (pintype "output"))
      (node (ref "IC17") (pin "15") (pinfunction "~{Q3}_15") (pintype "output"))
      (node (ref "IC17") (pin "3") (pinfunction "~{Q0}_3") (pintype "output"))
      (node (ref "IC17") (pin "9") (pinfunction "~{Q1}_9") (pintype "output"))
      (node (ref "IC20") (pin "12") (pinfunction "~{Q2}_12") (pintype "output"))
      (node (ref "IC20") (pin "15") (pinfunction "~{Q3}_15") (pintype "output"))
      (node (ref "IC20") (pin "3") (pinfunction "~{Q0}_3") (pintype "output"))
      (node (ref "IC20") (pin "9") (pinfunction "~{Q1}_9") (pintype "output"))
      (node (ref "IC21") (pin "12") (pinfunction "~{Q2}_12") (pintype "output"))
      (node (ref "IC21") (pin "15") (pinfunction "~{Q3}_15") (pintype "output"))
      (node (ref "IC21") (pin "3") (pinfunction "~{Q0}_3") (pintype "output"))
      (node (ref "IC21") (pin "9") (pinfunction "~{Q1}_9") (pintype "output"))
      (node (ref "IC24") (pin "12") (pinfunction "~{Q2}_12") (pintype "output"))
      (node (ref "IC24") (pin "15") (pinfunction "~{Q3}_15") (pintype "output"))
      (node (ref "IC24") (pin "3") (pinfunction "~{Q0}_3") (pintype "output"))
      (node (ref "IC24") (pin "9") (pinfunction "~{Q1}_9") (pintype "output"))
      (node (ref "IC25") (pin "12") (pinfunction "~{Q2}_12") (pintype "output"))
      (node (ref "IC25") (pin "15") (pinfunction "~{Q3}_15") (pintype "output"))
      (node (ref "IC25") (pin "3") (pinfunction "~{Q0}_3") (pintype "output"))
      (node (ref "IC25") (pin "9") (pinfunction "~{Q1}_9") (pintype "output"))
      (node (ref "IC28") (pin "12") (pinfunction "~{Q2}_12") (pintype "output"))
      (node (ref "IC28") (pin "15") (pinfunction "~{Q3}_15") (pintype "output"))
      (node (ref "IC28") (pin "3") (pinfunction "~{Q0}_3") (pintype "output"))
      (node (ref "IC28") (pin "9") (pinfunction "~{Q1}_9") (pintype "output"))
      (node (ref "IC29") (pin "12") (pinfunction "~{Q2}_12") (pintype "output"))
      (node (ref "IC29") (pin "15") (pinfunction "~{Q3}_15") (pintype "output"))
      (node (ref "IC29") (pin "3") (pinfunction "~{Q0}_3") (pintype "output"))
      (node (ref "IC29") (pin "9") (pinfunction "~{Q1}_9") (pintype "output"))
      (node (ref "IC32") (pin "12") (pinfunction "~{Q2}_12") (pintype "output"))
      (node (ref "IC32") (pin "15") (pinfunction "~{Q3}_15") (pintype "output"))
      (node (ref "IC32") (pin "3") (pinfunction "~{Q0}_3") (pintype "output"))
      (node (ref "IC32") (pin "9") (pinfunction "~{Q1}_9") (pintype "output"))
      (node (ref "IC33") (pin "12") (pinfunction "~{Q2}_12") (pintype "output"))
      (node (ref "IC33") (pin "15") (pinfunction "~{Q3}_15") (pintype "output"))
      (node (ref "IC33") (pin "3") (pinfunction "~{Q0}_3") (pintype "output"))
      (node (ref "IC33") (pin "9") (pinfunction "~{Q1}_9") (pintype "output"))
      (node (ref "IC36") (pin "12") (pinfunction "~{Q2}_12") (pintype "output"))
      (node (ref "IC36") (pin "15") (pinfunction "~{Q3}_15") (pintype "output"))
      (node (ref "IC36") (pin "3") (pinfunction "~{Q0}_3") (pintype "output"))
      (node (ref "IC36") (pin "9") (pinfunction "~{Q1}_9") (pintype "output"))
      (node (ref "IC37") (pin "12") (pinfunction "~{Q2}_12") (pintype "output"))
      (node (ref "IC37") (pin "15") (pinfunction "~{Q3}_15") (pintype "output"))
      (node (ref "IC37") (pin "3") (pinfunction "~{Q0}_3") (pintype "output"))
      (node (ref "IC37") (pin "9") (pinfunction "~{Q1}_9") (pintype "output"))
      (node (ref "IC4") (pin "12") (pinfunction "~{Q2}_12") (pintype "output"))
      (node (ref "IC4") (pin "15") (pinfunction "~{Q3}_15") (pintype "output"))
      (node (ref "IC4") (pin "3") (pinfunction "~{Q0}_3") (pintype "output"))
      (node (ref "IC4") (pin "9") (pinfunction "~{Q1}_9") (pintype "output"))
      (node (ref "IC40") (pin "12") (pinfunction "~{Q2}_12") (pintype "output"))
      (node (ref "IC40") (pin "15") (pinfunction "~{Q3}_15") (pintype "output"))
      (node (ref "IC40") (pin "3") (pinfunction "~{Q0}_3") (pintype "output"))
      (node (ref "IC40") (pin "9") (pinfunction "~{Q1}_9") (pintype "output"))
      (node (ref "IC41") (pin "12") (pinfunction "~{Q2}_12") (pintype "output"))
      (node (ref "IC41") (pin "15") (pinfunction "~{Q3}_15") (pintype "output"))
      (node (ref "IC41") (pin "3") (pinfunction "~{Q0}_3") (pintype "output"))
      (node (ref "IC41") (pin "9") (pinfunction "~{Q1}_9") (pintype "output"))
      (node (ref "IC44") (pin "12") (pinfunction "~{Q2}_12") (pintype "output"))
      (node (ref "IC44") (pin "15") (pinfunction "~{Q3}_15") (pintype "output"))
      (node (ref "IC44") (pin "3") (pinfunction "~{Q0}_3") (pintype "output"))
      (node (ref "IC44") (pin "9") (pinfunction "~{Q1}_9") (pintype "output"))
      (node (ref "IC45") (pin "12") (pinfunction "~{Q2}_12") (pintype "output"))
      (node (ref "IC45") (pin "15") (pinfunction "~{Q3}_15") (pintype "output"))
      (node (ref "IC45") (pin "3") (pinfunction "~{Q0}_3") (pintype "output"))
      (node (ref "IC45") (pin "9") (pinfunction "~{Q1}_9") (pintype "output"))
      (node (ref "IC48") (pin "12") (pinfunction "~{Q2}_12") (pintype "output"))
      (node (ref "IC48") (pin "15") (pinfunction "~{Q3}_15") (pintype "output"))
      (node (ref "IC48") (pin "3") (pinfunction "~{Q0}_3") (pintype "output"))
      (node (ref "IC48") (pin "9") (pinfunction "~{Q1}_9") (pintype "output"))
      (node (ref "IC49") (pin "12") (pinfunction "~{Q2}_12") (pintype "output"))
      (node (ref "IC49") (pin "15") (pinfunction "~{Q3}_15") (pintype "output"))
      (node (ref "IC49") (pin "3") (pinfunction "~{Q0}_3") (pintype "output"))
      (node (ref "IC49") (pin "9") (pinfunction "~{Q1}_9") (pintype "output"))
      (node (ref "IC5") (pin "12") (pinfunction "~{Q2}_12") (pintype "output"))
      (node (ref "IC5") (pin "15") (pinfunction "~{Q3}_15") (pintype "output"))
      (node (ref "IC5") (pin "3") (pinfunction "~{Q0}_3") (pintype "output"))
      (node (ref "IC5") (pin "9") (pinfunction "~{Q1}_9") (pintype "output"))
      (node (ref "IC52") (pin "12") (pinfunction "~{Q2}_12") (pintype "output"))
      (node (ref "IC52") (pin "15") (pinfunction "~{Q3}_15") (pintype "output"))
      (node (ref "IC52") (pin "3") (pinfunction "~{Q0}_3") (pintype "output"))
      (node (ref "IC52") (pin "9") (pinfunction "~{Q1}_9") (pintype "output"))
      (node (ref "IC53") (pin "12") (pinfunction "~{Q2}_12") (pintype "output"))
      (node (ref "IC53") (pin "15") (pinfunction "~{Q3}_15") (pintype "output"))
      (node (ref "IC53") (pin "3") (pinfunction "~{Q0}_3") (pintype "output"))
      (node (ref "IC53") (pin "9") (pinfunction "~{Q1}_9") (pintype "output"))
      (node (ref "IC56") (pin "12") (pinfunction "~{Q2}_12") (pintype "output"))
      (node (ref "IC56") (pin "15") (pinfunction "~{Q3}_15") (pintype "output"))
      (node (ref "IC56") (pin "3") (pinfunction "~{Q0}_3") (pintype "output"))
      (node (ref "IC56") (pin "9") (pinfunction "~{Q1}_9") (pintype "output"))
      (node (ref "IC57") (pin "12") (pinfunction "~{Q2}_12") (pintype "output"))
      (node (ref "IC57") (pin "15") (pinfunction "~{Q3}_15") (pintype "output"))
      (node (ref "IC57") (pin "3") (pinfunction "~{Q0}_3") (pintype "output"))
      (node (ref "IC57") (pin "9") (pinfunction "~{Q1}_9") (pintype "output"))
      (node (ref "IC60") (pin "12") (pinfunction "~{Q2}_12") (pintype "output"))
      (node (ref "IC60") (pin "15") (pinfunction "~{Q3}_15") (pintype "output"))
      (node (ref "IC60") (pin "3") (pinfunction "~{Q0}_3") (pintype "output"))
      (node (ref "IC60") (pin "9") (pinfunction "~{Q1}_9") (pintype "output"))
      (node (ref "IC61") (pin "12") (pinfunction "~{Q2}_12") (pintype "output"))
      (node (ref "IC61") (pin "15") (pinfunction "~{Q3}_15") (pintype "output"))
      (node (ref "IC61") (pin "3") (pinfunction "~{Q0}_3") (pintype "output"))
      (node (ref "IC61") (pin "9") (pinfunction "~{Q1}_9") (pintype "output"))
      (node (ref "IC64") (pin "12") (pinfunction "~{Q2}_12") (pintype "output"))
      (node (ref "IC64") (pin "15") (pinfunction "~{Q3}_15") (pintype "output"))
      (node (ref "IC64") (pin "3") (pinfunction "~{Q0}_3") (pintype "output"))
      (node (ref "IC64") (pin "9") (pinfunction "~{Q1}_9") (pintype "output"))
      (node (ref "IC8") (pin "12") (pinfunction "~{Q2}_12") (pintype "output"))
      (node (ref "IC8") (pin "15") (pinfunction "~{Q3}_15") (pintype "output"))
      (node (ref "IC8") (pin "3") (pinfunction "~{Q0}_3") (pintype "output"))
      (node (ref "IC8") (pin "9") (pinfunction "~{Q1}_9") (pintype "output"))
      (node (ref "IC9") (pin "12") (pinfunction "~{Q2}_12") (pintype "output"))
      (node (ref "IC9") (pin "15") (pinfunction "~{Q3}_15") (pintype "output"))
      (node (ref "IC9") (pin "3") (pinfunction "~{Q0}_3") (pintype "output"))
      (node (ref "IC9") (pin "9") (pinfunction "~{Q1}_9") (pintype "output"))
      (node (ref "KICK_DRUM") (pin "3") (pinfunction "3_3") (pintype "passive"))
      (node (ref "KNOB_CONNECTIONS") (pin "49") (pinfunction "49_49") (pintype "passive"))
      (node (ref "LO_TOM") (pin "3") (pinfunction "3_3") (pintype "passive"))
      (node (ref "POWER_SUPPY") (pin "2") (pinfunction "2_2") (pintype "passive"))
      (node (ref "POWER_SUPPY") (pin "3") (pinfunction "3_3") (pintype "passive"))
      (node (ref "R11") (pin "1") (pinfunction "1_1") (pintype "passive"))
      (node (ref "R13") (pin "1") (pinfunction "1_1") (pintype "passive"))
      (node (ref "R15") (pin "1") (pinfunction "1_1") (pintype "passive"))
      (node (ref "R17") (pin "1") (pinfunction "1_1") (pintype "passive"))
      (node (ref "R18") (pin "1") (pinfunction "1_1") (pintype "passive"))
      (node (ref "R20") (pin "1") (pinfunction "1_1") (pintype "passive"))
      (node (ref "R22") (pin "1") (pinfunction "1_1") (pintype "passive"))
      (node (ref "R24") (pin "1") (pinfunction "1_1") (pintype "passive"))
      (node (ref "R26") (pin "1") (pinfunction "1_1") (pintype "passive"))
      (node (ref "R28") (pin "1") (pinfunction "1_1") (pintype "passive"))
      (node (ref "R3") (pin "1") (pinfunction "1_1") (pintype "passive"))
      (node (ref "R30") (pin "1") (pinfunction "1_1") (pintype "passive"))
      (node (ref "R32") (pin "1") (pinfunction "1_1") (pintype "passive"))
      (node (ref "R5") (pin "1") (pinfunction "1_1") (pintype "passive"))
      (node (ref "R7") (pin "1") (pinfunction "1_1") (pintype "passive"))
      (node (ref "R9") (pin "1") (pinfunction "1_1") (pintype "passive"))
      (node (ref "SEQUENCER") (pin "17") (pinfunction "17_17") (pintype "passive"))
      (node (ref "SNARE_DRUM") (pin "3") (pinfunction "3_3") (pintype "passive"))
      (node (ref "SPECIAL_INSTRUMENT") (pin "3") (pinfunction "3_3") (pintype "passive"))
    )
    (net (code "3") (name "Net-(1B-1)") (class "Default")
      (node (ref "1") (pin "2") (pinfunction "1_2") (pintype "passive"))
      (node (ref "KNOB_CONNECTIONS") (pin "43") (pinfunction "43_43") (pintype "passive"))
      (node (ref "KNOB_CONNECTIONS") (pin "45") (pinfunction "45_45") (pintype "passive"))
      (node (ref "KNOB_CONNECTIONS") (pin "47") (pinfunction "47_47") (pintype "passive"))
      (node (ref "SEQUENCER") (pin "15") (pinfunction "15_15") (pintype "passive"))
    )
    (net (code "4") (name "Net-(1C-1)") (class "Default")
      (node (ref "1") (pin "3") (pinfunction "1_3") (pintype "passive"))
      (node (ref "KNOB_CONNECTIONS") (pin "37") (pinfunction "37_37") (pintype "passive"))
      (node (ref "KNOB_CONNECTIONS") (pin "39") (pinfunction "39_39") (pintype "passive"))
      (node (ref "KNOB_CONNECTIONS") (pin "41") (pinfunction "41_41") (pintype "passive"))
      (node (ref "SEQUENCER") (pin "13") (pinfunction "13_13") (pintype "passive"))
    )
    (net (code "5") (name "Net-(1D-1)") (class "Default")
      (node (ref "1") (pin "4") (pinfunction "1_4") (pintype "passive"))
      (node (ref "KNOB_CONNECTIONS") (pin "31") (pinfunction "31_31") (pintype "passive"))
      (node (ref "KNOB_CONNECTIONS") (pin "33") (pinfunction "33_33") (pintype "passive"))
      (node (ref "KNOB_CONNECTIONS") (pin "35") (pinfunction "35_35") (pintype "passive"))
      (node (ref "SEQUENCER") (pin "11") (pinfunction "11_11") (pintype "passive"))
    )
    (net (code "6") (name "Net-(1E-1)") (class "Default")
      (node (ref "1") (pin "5") (pinfunction "1_5") (pintype "passive"))
      (node (ref "KNOB_CONNECTIONS") (pin "25") (pinfunction "25_25") (pintype "passive"))
      (node (ref "KNOB_CONNECTIONS") (pin "27") (pinfunction "27_27") (pintype "passive"))
      (node (ref "KNOB_CONNECTIONS") (pin "29") (pinfunction "29_29") (pintype "passive"))
      (node (ref "SEQUENCER") (pin "9") (pinfunction "9_9") (pintype "passive"))
    )
    (net (code "7") (name "Net-(2-Pad1)") (class "Default")
      (node (ref "2") (pin "1") (pinfunction "1_1") (pintype "passive"))
      (node (ref "KNOB_CONNECTIONS") (pin "19") (pinfunction "19_19") (pintype "passive"))
      (node (ref "KNOB_CONNECTIONS") (pin "21") (pinfunction "21_21") (pintype "passive"))
      (node (ref "KNOB_CONNECTIONS") (pin "23") (pinfunction "23_23") (pintype "passive"))
      (node (ref "SEQUENCER") (pin "7") (pinfunction "7_7") (pintype "passive"))
    )
    (net (code "8") (name "Net-(2B-1)") (class "Default")
      (node (ref "2") (pin "2") (pinfunction "1_2") (pintype "passive"))
      (node (ref "KNOB_CONNECTIONS") (pin "13") (pinfunction "13_13") (pintype "passive"))
      (node (ref "KNOB_CONNECTIONS") (pin "15") (pinfunction "15_15") (pintype "passive"))
      (node (ref "KNOB_CONNECTIONS") (pin "17") (pinfunction "17_17") (pintype "passive"))
      (node (ref "SEQUENCER") (pin "5") (pinfunction "5_5") (pintype "passive"))
    )
    (net (code "9") (name "Net-(2C-1)") (class "Default")
      (node (ref "2") (pin "3") (pinfunction "1_3") (pintype "passive"))
      (node (ref "KNOB_CONNECTIONS") (pin "11") (pinfunction "11_11") (pintype "passive"))
      (node (ref "KNOB_CONNECTIONS") (pin "7") (pinfunction "7_7") (pintype "passive"))
      (node (ref "KNOB_CONNECTIONS") (pin "9") (pinfunction "9_9") (pintype "passive"))
      (node (ref "SEQUENCER") (pin "3") (pinfunction "3_3") (pintype "passive"))
    )
    (net (code "10") (name "Net-(2D-1)") (class "Default")
      (node (ref "2") (pin "4") (pinfunction "1_4") (pintype "passive"))
      (node (ref "KNOB_CONNECTIONS") (pin "1") (pinfunction "1_1") (pintype "passive"))
      (node (ref "KNOB_CONNECTIONS") (pin "3") (pinfunction "3_3") (pintype "passive"))
      (node (ref "KNOB_CONNECTIONS") (pin "5") (pinfunction "5_5") (pintype "passive"))
      (node (ref "SEQUENCER") (pin "1") (pinfunction "1_1") (pintype "passive"))
    )
    (net (code "11") (name "Net-(BUTTON_1-Pad2)") (class "Default")
      (node (ref "BUTTON_1") (pin "2") (pinfunction "2_2") (pintype "passive"))
      (node (ref "R1") (pin "1") (pinfunction "1_1") (pintype "passive"))
    )
    (net (code "12") (name "Net-(BUTTON_2-Pad2)") (class "Default")
      (node (ref "BUTTON_2") (pin "2") (pinfunction "2_2") (pintype "passive"))
      (node (ref "R2") (pin "1") (pinfunction "1_1") (pintype "passive"))
    )
    (net (code "13") (name "Net-(BUTTON_3-Pad2)") (class "Default")
      (node (ref "BUTTON_3") (pin "2") (pinfunction "2_2") (pintype "passive"))
      (node (ref "R4") (pin "1") (pinfunction "1_1") (pintype "passive"))
    )
    (net (code "14") (name "Net-(BUTTON_4-Pad2)") (class "Default")
      (node (ref "BUTTON_4") (pin "2") (pinfunction "2_2") (pintype "passive"))
      (node (ref "R6") (pin "1") (pinfunction "1_1") (pintype "passive"))
    )
    (net (code "15") (name "Net-(BUTTON_5-Pad2)") (class "Default")
      (node (ref "BUTTON_5") (pin "2") (pinfunction "2_2") (pintype "passive"))
      (node (ref "R8") (pin "1") (pinfunction "1_1") (pintype "passive"))
    )
    (net (code "16") (name "Net-(BUTTON_6-Pad2)") (class "Default")
      (node (ref "BUTTON_6") (pin "2") (pinfunction "2_2") (pintype "passive"))
      (node (ref "R10") (pin "1") (pinfunction "1_1") (pintype "passive"))
    )
    (net (code "17") (name "Net-(BUTTON_7-Pad2)") (class "Default")
      (node (ref "BUTTON_7") (pin "2") (pinfunction "2_2") (pintype "passive"))
      (node (ref "R12") (pin "1") (pinfunction "1_1") (pintype "passive"))
    )
    (net (code "18") (name "Net-(BUTTON_8-Pad2)") (class "Default")
      (node (ref "BUTTON_8") (pin "2") (pinfunction "2_2") (pintype "passive"))
      (node (ref "R14") (pin "1") (pinfunction "1_1") (pintype "passive"))
    )
    (net (code "19") (name "Net-(BUTTON_9-Pad2)") (class "Default")
      (node (ref "BUTTON_9") (pin "2") (pinfunction "2_2") (pintype "passive"))
      (node (ref "R16") (pin "1") (pinfunction "1_1") (pintype "passive"))
    )
    (net (code "20") (name "Net-(BUTTON_10-Pad2)") (class "Default")
      (node (ref "BUTTON_10") (pin "2") (pinfunction "2_2") (pintype "passive"))
      (node (ref "R19") (pin "1") (pinfunction "1_1") (pintype "passive"))
    )
    (net (code "21") (name "Net-(BUTTON_11-Pad2)") (class "Default")
      (node (ref "BUTTON_11") (pin "2") (pinfunction "2_2") (pintype "passive"))
      (node (ref "R21") (pin "1") (pinfunction "1_1") (pintype "passive"))
    )
    (net (code "22") (name "Net-(BUTTON_12-Pad2)") (class "Default")
      (node (ref "BUTTON_12") (pin "2") (pinfunction "2_2") (pintype "passive"))
      (node (ref "R23") (pin "1") (pinfunction "1_1") (pintype "passive"))
    )
    (net (code "23") (name "Net-(BUTTON_13-Pad2)") (class "Default")
      (node (ref "BUTTON_13") (pin "2") (pinfunction "2_2") (pintype "passive"))
      (node (ref "R25") (pin "1") (pinfunction "1_1") (pintype "passive"))
    )
    (net (code "24") (name "Net-(BUTTON_14-Pad2)") (class "Default")
      (node (ref "BUTTON_14") (pin "2") (pinfunction "2_2") (pintype "passive"))
      (node (ref "R27") (pin "1") (pinfunction "1_1") (pintype "passive"))
    )
    (net (code "25") (name "Net-(BUTTON_15-Pad2)") (class "Default")
      (node (ref "BUTTON_15") (pin "2") (pinfunction "2_2") (pintype "passive"))
      (node (ref "R29") (pin "1") (pinfunction "1_1") (pintype "passive"))
    )
    (net (code "26") (name "Net-(BUTTON_16-Pad2)") (class "Default")
      (node (ref "BUTTON_16") (pin "2") (pinfunction "2_2") (pintype "passive"))
      (node (ref "R31") (pin "1") (pinfunction "1_1") (pintype "passive"))
    )
    (net (code "27") (name "Net-(CLOSED_HI_HAT-Pad1)") (class "Default")
      (node (ref "CLOSED_HI_HAT") (pin "1") (pinfunction "1_1") (pintype "passive"))
      (node (ref "KNOB_CONNECTIONS") (pin "38") (pinfunction "38_38") (pintype "passive"))
      (node (ref "KNOB_CONNECTIONS") (pin "40") (pinfunction "40_40") (pintype "passive"))
      (node (ref "KNOB_CONNECTIONS") (pin "42") (pinfunction "42_42") (pintype "passive"))
      (node (ref "PIN_CONNECTIONS") (pin "14") (pinfunction "14_14") (pintype "passive"))
    )
    (net (code "28") (name "Net-(CLOSED_HI_HAT-Pad2)") (class "Default")
      (node (ref "CLOSED_HI_HAT") (pin "2") (pinfunction "2_2") (pintype "passive"))
      (node (ref "CLOSED_HI_HAT") (pin "4") (pinfunction "4_4") (pintype "passive"))
      (node (ref "MIXER") (pin "7") (pinfunction "7_7") (pintype "passive"))
    )
    (net (code "29") (name "Net-(CRASH-Pad1)") (class "Default")
      (node (ref "CRASH") (pin "1") (pinfunction "1_1") (pintype "passive"))
      (node (ref "KNOB_CONNECTIONS") (pin "26") (pinfunction "26_26") (pintype "passive"))
      (node (ref "KNOB_CONNECTIONS") (pin "28") (pinfunction "28_28") (pintype "passive"))
      (node (ref "KNOB_CONNECTIONS") (pin "30") (pinfunction "30_30") (pintype "passive"))
      (node (ref "PIN_CONNECTIONS") (pin "10") (pinfunction "10_10") (pintype "passive"))
    )
    (net (code "30") (name "Net-(CRASH-Pad2)") (class "Default")
      (node (ref "CRASH") (pin "2") (pinfunction "2_2") (pintype "passive"))
      (node (ref "CRASH") (pin "4") (pinfunction "4_4") (pintype "passive"))
      (node (ref "MIXER") (pin "5") (pinfunction "5_5") (pintype "passive"))
    )
    (net (code "31") (name "Net-(HI_HAT-Pad1)") (class "Default")
      (node (ref "HI_HAT") (pin "1") (pinfunction "1_1") (pintype "passive"))
      (node (ref "KNOB_CONNECTIONS") (pin "32") (pinfunction "32_32") (pintype "passive"))
      (node (ref "KNOB_CONNECTIONS") (pin "34") (pinfunction "34_34") (pintype "passive"))
      (node (ref "KNOB_CONNECTIONS") (pin "36") (pinfunction "36_36") (pintype "passive"))
      (node (ref "PIN_CONNECTIONS") (pin "12") (pinfunction "12_12") (pintype "passive"))
    )
    (net (code "32") (name "Net-(HI_HAT-Pad2)") (class "Default")
      (node (ref "HI_HAT") (pin "2") (pinfunction "2_2") (pintype "passive"))
      (node (ref "HI_HAT") (pin "4") (pinfunction "4_4") (pintype "passive"))
      (node (ref "MIXER") (pin "6") (pinfunction "6_6") (pintype "passive"))
    )
    (net (code "33") (name "Net-(HI_TOM-Pad1)") (class "Default")
      (node (ref "HI_TOM") (pin "1") (pinfunction "1_1") (pintype "passive"))
      (node (ref "KNOB_CONNECTIONS") (pin "10") (pinfunction "10_10") (pintype "passive"))
      (node (ref "KNOB_CONNECTIONS") (pin "12") (pinfunction "12_12") (pintype "passive"))
      (node (ref "KNOB_CONNECTIONS") (pin "8") (pinfunction "8_8") (pintype "passive"))
      (node (ref "PIN_CONNECTIONS") (pin "4") (pinfunction "4_4") (pintype "passive"))
    )
    (net (code "34") (name "Net-(HI_TOM-Pad2)") (class "Default")
      (node (ref "HI_TOM") (pin "2") (pinfunction "2_2") (pintype "passive"))
      (node (ref "HI_TOM") (pin "4") (pinfunction "4_4") (pintype "passive"))
      (node (ref "MIXER") (pin "2") (pinfunction "2_2") (pintype "passive"))
    )
    (net (code "35") (name "Net-(IC1A-D0)") (class "Default")
      (node (ref "C2") (pin "1") (pinfunction "1_1") (pintype "passive"))
      (node (ref "IC1") (pin "13") (pinfunction "D2_13") (pintype "input"))
      (node (ref "IC1") (pin "14") (pinfunction "D3_14") (pintype "input"))
      (node (ref "IC1") (pin "4") (pinfunction "D0_4") (pintype "input"))
      (node (ref "IC1") (pin "6") (pinfunction "POL_6") (pintype "input"))
      (node (ref "IC1") (pin "7") (pinfunction "D1_7") (pintype "input"))
      (node (ref "R1") (pin "2") (pinfunction "2_2") (pintype "passive"))
      (node (ref "R17") (pin "2") (pinfunction "2_2") (pintype "passive"))
    )
    (net (code "36") (name "Net-(IC1A-Q0)") (class "Default")
      (node (ref "IC1") (pin "1") (pinfunction "Q3_1") (pintype "output"))
      (node (ref "IC1") (pin "10") (pinfunction "Q1_10") (pintype "output"))
      (node (ref "IC1") (pin "11") (pinfunction "Q2_11") (pintype "output"))
      (node (ref "IC1") (pin "2") (pinfunction "Q0_2") (pintype "output"))
      (node (ref "IC2") (pin "13") (pinfunction "D2_13") (pintype "input"))
      (node (ref "IC2") (pin "14") (pinfunction "D3_14") (pintype "input"))
      (node (ref "IC2") (pin "4") (pinfunction "D0_4") (pintype "input"))
      (node (ref "IC2") (pin "6") (pinfunction "POL_6") (pintype "input"))
      (node (ref "IC2") (pin "7") (pinfunction "D1_7") (pintype "input"))
    )
    (net (code "37") (name "Net-(IC2A-Q0)") (class "Default")
      (node (ref "IC2") (pin "1") (pinfunction "Q3_1") (pintype "output"))
      (node (ref "IC2") (pin "10") (pinfunction "Q1_10") (pintype "output"))
      (node (ref "IC2") (pin "11") (pinfunction "Q2_11") (pintype "output"))
      (node (ref "IC2") (pin "2") (pinfunction "Q0_2") (pintype "output"))
      (node (ref "IC3") (pin "1") (pinfunction "I0_1") (pintype "input"))
    )
    (net (code "38") (name "Net-(IC2A-~{Q0})") (class "Default")
      (node (ref "IC2") (pin "12") (pinfunction "~{Q2}_12") (pintype "output"))
      (node (ref "IC2") (pin "15") (pinfunction "~{Q3}_15") (pintype "output"))
      (node (ref "IC2") (pin "3") (pinfunction "~{Q0}_3") (pintype "output"))
      (node (ref "IC2") (pin "9") (pinfunction "~{Q1}_9") (pintype "output"))
      (node (ref "IC4") (pin "13") (pinfunction "D2_13") (pintype "input"))
      (node (ref "IC4") (pin "14") (pinfunction "D3_14") (pintype "input"))
      (node (ref "IC4") (pin "4") (pinfunction "D0_4") (pintype "input"))
      (node (ref "IC4") (pin "6") (pinfunction "POL_6") (pintype "input"))
      (node (ref "IC4") (pin "7") (pinfunction "D1_7") (pintype "input"))
    )
    (net (code "39") (name "Net-(IC3A-I1)") (class "Default")
      (node (ref "IC3") (pin "2") (pinfunction "I1_2") (pintype "input"))
      (node (ref "IC4") (pin "1") (pinfunction "Q3_1") (pintype "output"))
      (node (ref "IC4") (pin "10") (pinfunction "Q1_10") (pintype "output"))
      (node (ref "IC4") (pin "11") (pinfunction "Q2_11") (pintype "output"))
      (node (ref "IC4") (pin "2") (pinfunction "Q0_2") (pintype "output"))
    )
    (net (code "40") (name "Net-(IC5A-D0)") (class "Default")
      (node (ref "C3") (pin "1") (pinfunction "1_1") (pintype "passive"))
      (node (ref "IC5") (pin "13") (pinfunction "D2_13") (pintype "input"))
      (node (ref "IC5") (pin "14") (pinfunction "D3_14") (pintype "input"))
      (node (ref "IC5") (pin "4") (pinfunction "D0_4") (pintype "input"))
      (node (ref "IC5") (pin "6") (pinfunction "POL_6") (pintype "input"))
      (node (ref "IC5") (pin "7") (pinfunction "D1_7") (pintype "input"))
      (node (ref "R2") (pin "2") (pinfunction "2_2") (pintype "passive"))
      (node (ref "R3") (pin "2") (pinfunction "2_2") (pintype "passive"))
    )
    (net (code "41") (name "Net-(IC5A-Q0)") (class "Default")
      (node (ref "IC5") (pin "1") (pinfunction "Q3_1") (pintype "output"))
      (node (ref "IC5") (pin "10") (pinfunction "Q1_10") (pintype "output"))
      (node (ref "IC5") (pin "11") (pinfunction "Q2_11") (pintype "output"))
      (node (ref "IC5") (pin "2") (pinfunction "Q0_2") (pintype "output"))
      (node (ref "IC6") (pin "13") (pinfunction "D2_13") (pintype "input"))
      (node (ref "IC6") (pin "14") (pinfunction "D3_14") (pintype "input"))
      (node (ref "IC6") (pin "4") (pinfunction "D0_4") (pintype "input"))
      (node (ref "IC6") (pin "6") (pinfunction "POL_6") (pintype "input"))
      (node (ref "IC6") (pin "7") (pinfunction "D1_7") (pintype "input"))
    )
    (net (code "42") (name "Net-(IC6A-Q0)") (class "Default")
      (node (ref "IC6") (pin "1") (pinfunction "Q3_1") (pintype "output"))
      (node (ref "IC6") (pin "10") (pinfunction "Q1_10") (pintype "output"))
      (node (ref "IC6") (pin "11") (pinfunction "Q2_11") (pintype "output"))
      (node (ref "IC6") (pin "2") (pinfunction "Q0_2") (pintype "output"))
      (node (ref "IC7") (pin "1") (pinfunction "I0_1") (pintype "input"))
    )
    (net (code "43") (name "Net-(IC6A-~{Q0})") (class "Default")
      (node (ref "IC6") (pin "12") (pinfunction "~{Q2}_12") (pintype "output"))
      (node (ref "IC6") (pin "15") (pinfunction "~{Q3}_15") (pintype "output"))
      (node (ref "IC6") (pin "3") (pinfunction "~{Q0}_3") (pintype "output"))
      (node (ref "IC6") (pin "9") (pinfunction "~{Q1}_9") (pintype "output"))
      (node (ref "IC8") (pin "13") (pinfunction "D2_13") (pintype "input"))
      (node (ref "IC8") (pin "14") (pinfunction "D3_14") (pintype "input"))
      (node (ref "IC8") (pin "4") (pinfunction "D0_4") (pintype "input"))
      (node (ref "IC8") (pin "6") (pinfunction "POL_6") (pintype "input"))
      (node (ref "IC8") (pin "7") (pinfunction "D1_7") (pintype "input"))
    )
    (net (code "44") (name "Net-(IC7A-I1)") (class "Default")
      (node (ref "IC7") (pin "2") (pinfunction "I1_2") (pintype "input"))
      (node (ref "IC8") (pin "1") (pinfunction "Q3_1") (pintype "output"))
      (node (ref "IC8") (pin "10") (pinfunction "Q1_10") (pintype "output"))
      (node (ref "IC8") (pin "11") (pinfunction "Q2_11") (pintype "output"))
      (node (ref "IC8") (pin "2") (pinfunction "Q0_2") (pintype "output"))
    )
    (net (code "45") (name "Net-(IC9A-D0)") (class "Default")
      (node (ref "C4") (pin "1") (pinfunction "1_1") (pintype "passive"))
      (node (ref "IC9") (pin "13") (pinfunction "D2_13") (pintype "input"))
      (node (ref "IC9") (pin "14") (pinfunction "D3_14") (pintype "input"))
      (node (ref "IC9") (pin "4") (pinfunction "D0_4") (pintype "input"))
      (node (ref "IC9") (pin "6") (pinfunction "POL_6") (pintype "input"))
      (node (ref "IC9") (pin "7") (pinfunction "D1_7") (pintype "input"))
      (node (ref "R4") (pin "2") (pinfunction "2_2") (pintype "passive"))
      (node (ref "R5") (pin "2") (pinfunction "2_2") (pintype "passive"))
    )
    (net (code "46") (name "Net-(IC10A-D0)") (class "Default")
      (node (ref "IC10") (pin "13") (pinfunction "D2_13") (pintype "input"))
      (node (ref "IC10") (pin "14") (pinfunction "D3_14") (pintype "input"))
      (node (ref "IC10") (pin "4") (pinfunction "D0_4") (pintype "input"))
      (node (ref "IC10") (pin "6") (pinfunction "POL_6") (pintype "input"))
      (node (ref "IC10") (pin "7") (pinfunction "D1_7") (pintype "input"))
      (node (ref "IC9") (pin "1") (pinfunction "Q3_1") (pintype "output"))
      (node (ref "IC9") (pin "10") (pinfunction "Q1_10") (pintype "output"))
      (node (ref "IC9") (pin "11") (pinfunction "Q2_11") (pintype "output"))
      (node (ref "IC9") (pin "2") (pinfunction "Q0_2") (pintype "output"))
    )
    (net (code "47") (name "Net-(IC10A-Q0)") (class "Default")
      (node (ref "IC10") (pin "1") (pinfunction "Q3_1") (pintype "output"))
      (node (ref "IC10") (pin "10") (pinfunction "Q1_10") (pintype "output"))
      (node (ref "IC10") (pin "11") (pinfunction "Q2_11") (pintype "output"))
      (node (ref "IC10") (pin "2") (pinfunction "Q0_2") (pintype "output"))
      (node (ref "IC11") (pin "1") (pinfunction "I0_1") (pintype "input"))
    )
    (net (code "48") (name "Net-(IC10A-~{Q0})") (class "Default")
      (node (ref "IC10") (pin "12") (pinfunction "~{Q2}_12") (pintype "output"))
      (node (ref "IC10") (pin "15") (pinfunction "~{Q3}_15") (pintype "output"))
      (node (ref "IC10") (pin "3") (pinfunction "~{Q0}_3") (pintype "output"))
      (node (ref "IC10") (pin "9") (pinfunction "~{Q1}_9") (pintype "output"))
      (node (ref "IC12") (pin "13") (pinfunction "D2_13") (pintype "input"))
      (node (ref "IC12") (pin "14") (pinfunction "D3_14") (pintype "input"))
      (node (ref "IC12") (pin "4") (pinfunction "D0_4") (pintype "input"))
      (node (ref "IC12") (pin "6") (pinfunction "POL_6") (pintype "input"))
      (node (ref "IC12") (pin "7") (pinfunction "D1_7") (pintype "input"))
    )
    (net (code "49") (name "Net-(IC11A-I1)") (class "Default")
      (node (ref "IC11") (pin "2") (pinfunction "I1_2") (pintype "input"))
      (node (ref "IC12") (pin "1") (pinfunction "Q3_1") (pintype "output"))
      (node (ref "IC12") (pin "10") (pinfunction "Q1_10") (pintype "output"))
      (node (ref "IC12") (pin "11") (pinfunction "Q2_11") (pintype "output"))
      (node (ref "IC12") (pin "2") (pinfunction "Q0_2") (pintype "output"))
    )
    (net (code "50") (name "Net-(IC13A-D0)") (class "Default")
      (node (ref "C5") (pin "1") (pinfunction "1_1") (pintype "passive"))
      (node (ref "IC13") (pin "13") (pinfunction "D2_13") (pintype "input"))
      (node (ref "IC13") (pin "14") (pinfunction "D3_14") (pintype "input"))
      (node (ref "IC13") (pin "4") (pinfunction "D0_4") (pintype "input"))
      (node (ref "IC13") (pin "6") (pinfunction "POL_6") (pintype "input"))
      (node (ref "IC13") (pin "7") (pinfunction "D1_7") (pintype "input"))
      (node (ref "R6") (pin "2") (pinfunction "2_2") (pintype "passive"))
      (node (ref "R7") (pin "2") (pinfunction "2_2") (pintype "passive"))
    )
    (net (code "51") (name "Net-(IC13A-Q0)") (class "Default")
      (node (ref "IC13") (pin "1") (pinfunction "Q3_1") (pintype "output"))
      (node (ref "IC13") (pin "10") (pinfunction "Q1_10") (pintype "output"))
      (node (ref "IC13") (pin "11") (pinfunction "Q2_11") (pintype "output"))
      (node (ref "IC13") (pin "2") (pinfunction "Q0_2") (pintype "output"))
      (node (ref "IC14") (pin "13") (pinfunction "D2_13") (pintype "input"))
      (node (ref "IC14") (pin "14") (pinfunction "D3_14") (pintype "input"))
      (node (ref "IC14") (pin "4") (pinfunction "D0_4") (pintype "input"))
      (node (ref "IC14") (pin "6") (pinfunction "POL_6") (pintype "input"))
      (node (ref "IC14") (pin "7") (pinfunction "D1_7") (pintype "input"))
    )
    (net (code "52") (name "Net-(IC14A-Q0)") (class "Default")
      (node (ref "IC14") (pin "1") (pinfunction "Q3_1") (pintype "output"))
      (node (ref "IC14") (pin "10") (pinfunction "Q1_10") (pintype "output"))
      (node (ref "IC14") (pin "11") (pinfunction "Q2_11") (pintype "output"))
      (node (ref "IC14") (pin "2") (pinfunction "Q0_2") (pintype "output"))
      (node (ref "IC15") (pin "1") (pinfunction "I0_1") (pintype "input"))
    )
    (net (code "53") (name "Net-(IC14A-~{Q0})") (class "Default")
      (node (ref "IC14") (pin "12") (pinfunction "~{Q2}_12") (pintype "output"))
      (node (ref "IC14") (pin "15") (pinfunction "~{Q3}_15") (pintype "output"))
      (node (ref "IC14") (pin "3") (pinfunction "~{Q0}_3") (pintype "output"))
      (node (ref "IC14") (pin "9") (pinfunction "~{Q1}_9") (pintype "output"))
      (node (ref "IC16") (pin "13") (pinfunction "D2_13") (pintype "input"))
      (node (ref "IC16") (pin "14") (pinfunction "D3_14") (pintype "input"))
      (node (ref "IC16") (pin "4") (pinfunction "D0_4") (pintype "input"))
      (node (ref "IC16") (pin "6") (pinfunction "POL_6") (pintype "input"))
      (node (ref "IC16") (pin "7") (pinfunction "D1_7") (pintype "input"))
    )
    (net (code "54") (name "Net-(IC15A-I1)") (class "Default")
      (node (ref "IC15") (pin "2") (pinfunction "I1_2") (pintype "input"))
      (node (ref "IC16") (pin "1") (pinfunction "Q3_1") (pintype "output"))
      (node (ref "IC16") (pin "10") (pinfunction "Q1_10") (pintype "output"))
      (node (ref "IC16") (pin "11") (pinfunction "Q2_11") (pintype "output"))
      (node (ref "IC16") (pin "2") (pinfunction "Q0_2") (pintype "output"))
    )
    (net (code "55") (name "Net-(IC17A-D0)") (class "Default")
      (node (ref "C6") (pin "1") (pinfunction "1_1") (pintype "passive"))
      (node (ref "IC17") (pin "13") (pinfunction "D2_13") (pintype "input"))
      (node (ref "IC17") (pin "14") (pinfunction "D3_14") (pintype "input"))
      (node (ref "IC17") (pin "4") (pinfunction "D0_4") (pintype "input"))
      (node (ref "IC17") (pin "6") (pinfunction "POL_6") (pintype "input"))
      (node (ref "IC17") (pin "7") (pinfunction "D1_7") (pintype "input"))
      (node (ref "R8") (pin "2") (pinfunction "2_2") (pintype "passive"))
      (node (ref "R9") (pin "2") (pinfunction "2_2") (pintype "passive"))
    )
    (net (code "56") (name "Net-(IC17A-Q0)") (class "Default")
      (node (ref "IC17") (pin "1") (pinfunction "Q3_1") (pintype "output"))
      (node (ref "IC17") (pin "10") (pinfunction "Q1_10") (pintype "output"))
      (node (ref "IC17") (pin "11") (pinfunction "Q2_11") (pintype "output"))
      (node (ref "IC17") (pin "2") (pinfunction "Q0_2") (pintype "output"))
      (node (ref "IC18") (pin "13") (pinfunction "D2_13") (pintype "input"))
      (node (ref "IC18") (pin "14") (pinfunction "D3_14") (pintype "input"))
      (node (ref "IC18") (pin "4") (pinfunction "D0_4") (pintype "input"))
      (node (ref "IC18") (pin "6") (pinfunction "POL_6") (pintype "input"))
      (node (ref "IC18") (pin "7") (pinfunction "D1_7") (pintype "input"))
    )
    (net (code "57") (name "Net-(IC18A-Q0)") (class "Default")
      (node (ref "IC18") (pin "1") (pinfunction "Q3_1") (pintype "output"))
      (node (ref "IC18") (pin "10") (pinfunction "Q1_10") (pintype "output"))
      (node (ref "IC18") (pin "11") (pinfunction "Q2_11") (pintype "output"))
      (node (ref "IC18") (pin "2") (pinfunction "Q0_2") (pintype "output"))
      (node (ref "IC19") (pin "1") (pinfunction "I0_1") (pintype "input"))
    )
    (net (code "58") (name "Net-(IC18A-~{Q0})") (class "Default")
      (node (ref "IC18") (pin "12") (pinfunction "~{Q2}_12") (pintype "output"))
      (node (ref "IC18") (pin "15") (pinfunction "~{Q3}_15") (pintype "output"))
      (node (ref "IC18") (pin "3") (pinfunction "~{Q0}_3") (pintype "output"))
      (node (ref "IC18") (pin "9") (pinfunction "~{Q1}_9") (pintype "output"))
      (node (ref "IC20") (pin "13") (pinfunction "D2_13") (pintype "input"))
      (node (ref "IC20") (pin "14") (pinfunction "D3_14") (pintype "input"))
      (node (ref "IC20") (pin "4") (pinfunction "D0_4") (pintype "input"))
      (node (ref "IC20") (pin "6") (pinfunction "POL_6") (pintype "input"))
      (node (ref "IC20") (pin "7") (pinfunction "D1_7") (pintype "input"))
    )
    (net (code "59") (name "Net-(IC19A-I1)") (class "Default")
      (node (ref "IC19") (pin "2") (pinfunction "I1_2") (pintype "input"))
      (node (ref "IC20") (pin "1") (pinfunction "Q3_1") (pintype "output"))
      (node (ref "IC20") (pin "10") (pinfunction "Q1_10") (pintype "output"))
      (node (ref "IC20") (pin "11") (pinfunction "Q2_11") (pintype "output"))
      (node (ref "IC20") (pin "2") (pinfunction "Q0_2") (pintype "output"))
    )
    (net (code "60") (name "Net-(IC21A-D0)") (class "Default")
      (node (ref "C7") (pin "1") (pinfunction "1_1") (pintype "passive"))
      (node (ref "IC21") (pin "13") (pinfunction "D2_13") (pintype "input"))
      (node (ref "IC21") (pin "14") (pinfunction "D3_14") (pintype "input"))
      (node (ref "IC21") (pin "4") (pinfunction "D0_4") (pintype "input"))
      (node (ref "IC21") (pin "6") (pinfunction "POL_6") (pintype "input"))
      (node (ref "IC21") (pin "7") (pinfunction "D1_7") (pintype "input"))
      (node (ref "R10") (pin "2") (pinfunction "2_2") (pintype "passive"))
      (node (ref "R11") (pin "2") (pinfunction "2_2") (pintype "passive"))
    )
    (net (code "61") (name "Net-(IC21A-Q0)") (class "Default")
      (node (ref "IC21") (pin "1") (pinfunction "Q3_1") (pintype "output"))
      (node (ref "IC21") (pin "10") (pinfunction "Q1_10") (pintype "output"))
      (node (ref "IC21") (pin "11") (pinfunction "Q2_11") (pintype "output"))
      (node (ref "IC21") (pin "2") (pinfunction "Q0_2") (pintype "output"))
      (node (ref "IC22") (pin "13") (pinfunction "D2_13") (pintype "input"))
      (node (ref "IC22") (pin "14") (pinfunction "D3_14") (pintype "input"))
      (node (ref "IC22") (pin "4") (pinfunction "D0_4") (pintype "input"))
      (node (ref "IC22") (pin "6") (pinfunction "POL_6") (pintype "input"))
      (node (ref "IC22") (pin "7") (pinfunction "D1_7") (pintype "input"))
    )
    (net (code "62") (name "Net-(IC22A-Q0)") (class "Default")
      (node (ref "IC22") (pin "1") (pinfunction "Q3_1") (pintype "output"))
      (node (ref "IC22") (pin "10") (pinfunction "Q1_10") (pintype "output"))
      (node (ref "IC22") (pin "11") (pinfunction "Q2_11") (pintype "output"))
      (node (ref "IC22") (pin "2") (pinfunction "Q0_2") (pintype "output"))
      (node (ref "IC23") (pin "1") (pinfunction "I0_1") (pintype "input"))
    )
    (net (code "63") (name "Net-(IC22A-~{Q0})") (class "Default")
      (node (ref "IC22") (pin "12") (pinfunction "~{Q2}_12") (pintype "output"))
      (node (ref "IC22") (pin "15") (pinfunction "~{Q3}_15") (pintype "output"))
      (node (ref "IC22") (pin "3") (pinfunction "~{Q0}_3") (pintype "output"))
      (node (ref "IC22") (pin "9") (pinfunction "~{Q1}_9") (pintype "output"))
      (node (ref "IC24") (pin "13") (pinfunction "D2_13") (pintype "input"))
      (node (ref "IC24") (pin "14") (pinfunction "D3_14") (pintype "input"))
      (node (ref "IC24") (pin "4") (pinfunction "D0_4") (pintype "input"))
      (node (ref "IC24") (pin "6") (pinfunction "POL_6") (pintype "input"))
      (node (ref "IC24") (pin "7") (pinfunction "D1_7") (pintype "input"))
    )
    (net (code "64") (name "Net-(IC23A-I1)") (class "Default")
      (node (ref "IC23") (pin "2") (pinfunction "I1_2") (pintype "input"))
      (node (ref "IC24") (pin "1") (pinfunction "Q3_1") (pintype "output"))
      (node (ref "IC24") (pin "10") (pinfunction "Q1_10") (pintype "output"))
      (node (ref "IC24") (pin "11") (pinfunction "Q2_11") (pintype "output"))
      (node (ref "IC24") (pin "2") (pinfunction "Q0_2") (pintype "output"))
    )
    (net (code "65") (name "Net-(IC25A-D0)") (class "Default")
      (node (ref "C8") (pin "1") (pinfunction "1_1") (pintype "passive"))
      (node (ref "IC25") (pin "13") (pinfunction "D2_13") (pintype "input"))
      (node (ref "IC25") (pin "14") (pinfunction "D3_14") (pintype "input"))
      (node (ref "IC25") (pin "4") (pinfunction "D0_4") (pintype "input"))
      (node (ref "IC25") (pin "6") (pinfunction "POL_6") (pintype "input"))
      (node (ref "IC25") (pin "7") (pinfunction "D1_7") (pintype "input"))
      (node (ref "R12") (pin "2") (pinfunction "2_2") (pintype "passive"))
      (node (ref "R13") (pin "2") (pinfunction "2_2") (pintype "passive"))
    )
    (net (code "66") (name "Net-(IC25A-Q0)") (class "Default")
      (node (ref "IC25") (pin "1") (pinfunction "Q3_1") (pintype "output"))
      (node (ref "IC25") (pin "10") (pinfunction "Q1_10") (pintype "output"))
      (node (ref "IC25") (pin "11") (pinfunction "Q2_11") (pintype "output"))
      (node (ref "IC25") (pin "2") (pinfunction "Q0_2") (pintype "output"))
      (node (ref "IC26") (pin "13") (pinfunction "D2_13") (pintype "input"))
      (node (ref "IC26") (pin "14") (pinfunction "D3_14") (pintype "input"))
      (node (ref "IC26") (pin "4") (pinfunction "D0_4") (pintype "input"))
      (node (ref "IC26") (pin "6") (pinfunction "POL_6") (pintype "input"))
      (node (ref "IC26") (pin "7") (pinfunction "D1_7") (pintype "input"))
    )
    (net (code "67") (name "Net-(IC26A-Q0)") (class "Default")
      (node (ref "IC26") (pin "1") (pinfunction "Q3_1") (pintype "output"))
      (node (ref "IC26") (pin "10") (pinfunction "Q1_10") (pintype "output"))
      (node (ref "IC26") (pin "11") (pinfunction "Q2_11") (pintype "output"))
      (node (ref "IC26") (pin "2") (pinfunction "Q0_2") (pintype "output"))
      (node (ref "IC27") (pin "1") (pinfunction "I0_1") (pintype "input"))
    )
    (net (code "68") (name "Net-(IC26A-~{Q0})") (class "Default")
      (node (ref "IC26") (pin "12") (pinfunction "~{Q2}_12") (pintype "output"))
      (node (ref "IC26") (pin "15") (pinfunction "~{Q3}_15") (pintype "output"))
      (node (ref "IC26") (pin "3") (pinfunction "~{Q0}_3") (pintype "output"))
      (node (ref "IC26") (pin "9") (pinfunction "~{Q1}_9") (pintype "output"))
      (node (ref "IC28") (pin "13") (pinfunction "D2_13") (pintype "input"))
      (node (ref "IC28") (pin "14") (pinfunction "D3_14") (pintype "input"))
      (node (ref "IC28") (pin "4") (pinfunction "D0_4") (pintype "input"))
      (node (ref "IC28") (pin "6") (pinfunction "POL_6") (pintype "input"))
      (node (ref "IC28") (pin "7") (pinfunction "D1_7") (pintype "input"))
    )
    (net (code "69") (name "Net-(IC27A-I1)") (class "Default")
      (node (ref "IC27") (pin "2") (pinfunction "I1_2") (pintype "input"))
      (node (ref "IC28") (pin "1") (pinfunction "Q3_1") (pintype "output"))
      (node (ref "IC28") (pin "10") (pinfunction "Q1_10") (pintype "output"))
      (node (ref "IC28") (pin "11") (pinfunction "Q2_11") (pintype "output"))
      (node (ref "IC28") (pin "2") (pinfunction "Q0_2") (pintype "output"))
    )
    (net (code "70") (name "Net-(IC29A-D0)") (class "Default")
      (node (ref "C9") (pin "1") (pinfunction "1_1") (pintype "passive"))
      (node (ref "IC29") (pin "13") (pinfunction "D2_13") (pintype "input"))
      (node (ref "IC29") (pin "14") (pinfunction "D3_14") (pintype "input"))
      (node (ref "IC29") (pin "4") (pinfunction "D0_4") (pintype "input"))
      (node (ref "IC29") (pin "6") (pinfunction "POL_6") (pintype "input"))
      (node (ref "IC29") (pin "7") (pinfunction "D1_7") (pintype "input"))
      (node (ref "R14") (pin "2") (pinfunction "2_2") (pintype "passive"))
      (node (ref "R15") (pin "2") (pinfunction "2_2") (pintype "passive"))
    )
    (net (code "71") (name "Net-(IC29A-Q0)") (class "Default")
      (node (ref "IC29") (pin "1") (pinfunction "Q3_1") (pintype "output"))
      (node (ref "IC29") (pin "10") (pinfunction "Q1_10") (pintype "output"))
      (node (ref "IC29") (pin "11") (pinfunction "Q2_11") (pintype "output"))
      (node (ref "IC29") (pin "2") (pinfunction "Q0_2") (pintype "output"))
      (node (ref "IC30") (pin "13") (pinfunction "D2_13") (pintype "input"))
      (node (ref "IC30") (pin "14") (pinfunction "D3_14") (pintype "input"))
      (node (ref "IC30") (pin "4") (pinfunction "D0_4") (pintype "input"))
      (node (ref "IC30") (pin "6") (pinfunction "POL_6") (pintype "input"))
      (node (ref "IC30") (pin "7") (pinfunction "D1_7") (pintype "input"))
    )
    (net (code "72") (name "Net-(IC30A-Q0)") (class "Default")
      (node (ref "IC30") (pin "1") (pinfunction "Q3_1") (pintype "output"))
      (node (ref "IC30") (pin "10") (pinfunction "Q1_10") (pintype "output"))
      (node (ref "IC30") (pin "11") (pinfunction "Q2_11") (pintype "output"))
      (node (ref "IC30") (pin "2") (pinfunction "Q0_2") (pintype "output"))
      (node (ref "IC31") (pin "1") (pinfunction "I0_1") (pintype "input"))
    )
    (net (code "73") (name "Net-(IC30A-~{Q0})") (class "Default")
      (node (ref "IC30") (pin "12") (pinfunction "~{Q2}_12") (pintype "output"))
      (node (ref "IC30") (pin "15") (pinfunction "~{Q3}_15") (pintype "output"))
      (node (ref "IC30") (pin "3") (pinfunction "~{Q0}_3") (pintype "output"))
      (node (ref "IC30") (pin "9") (pinfunction "~{Q1}_9") (pintype "output"))
      (node (ref "IC32") (pin "13") (pinfunction "D2_13") (pintype "input"))
      (node (ref "IC32") (pin "14") (pinfunction "D3_14") (pintype "input"))
      (node (ref "IC32") (pin "4") (pinfunction "D0_4") (pintype "input"))
      (node (ref "IC32") (pin "6") (pinfunction "POL_6") (pintype "input"))
      (node (ref "IC32") (pin "7") (pinfunction "D1_7") (pintype "input"))
    )
    (net (code "74") (name "Net-(IC31A-I1)") (class "Default")
      (node (ref "IC31") (pin "2") (pinfunction "I1_2") (pintype "input"))
      (node (ref "IC32") (pin "1") (pinfunction "Q3_1") (pintype "output"))
      (node (ref "IC32") (pin "10") (pinfunction "Q1_10") (pintype "output"))
      (node (ref "IC32") (pin "11") (pinfunction "Q2_11") (pintype "output"))
      (node (ref "IC32") (pin "2") (pinfunction "Q0_2") (pintype "output"))
    )
    (net (code "75") (name "Net-(IC33A-D0)") (class "Default")
      (node (ref "C10") (pin "1") (pinfunction "1_1") (pintype "passive"))
      (node (ref "IC33") (pin "13") (pinfunction "D2_13") (pintype "input"))
      (node (ref "IC33") (pin "14") (pinfunction "D3_14") (pintype "input"))
      (node (ref "IC33") (pin "4") (pinfunction "D0_4") (pintype "input"))
      (node (ref "IC33") (pin "6") (pinfunction "POL_6") (pintype "input"))
      (node (ref "IC33") (pin "7") (pinfunction "D1_7") (pintype "input"))
      (node (ref "R16") (pin "2") (pinfunction "2_2") (pintype "passive"))
      (node (ref "R18") (pin "2") (pinfunction "2_2") (pintype "passive"))
    )
    (net (code "76") (name "Net-(IC33A-Q0)") (class "Default")
      (node (ref "IC33") (pin "1") (pinfunction "Q3_1") (pintype "output"))
      (node (ref "IC33") (pin "10") (pinfunction "Q1_10") (pintype "output"))
      (node (ref "IC33") (pin "11") (pinfunction "Q2_11") (pintype "output"))
      (node (ref "IC33") (pin "2") (pinfunction "Q0_2") (pintype "output"))
      (node (ref "IC34") (pin "13") (pinfunction "D2_13") (pintype "input"))
      (node (ref "IC34") (pin "14") (pinfunction "D3_14") (pintype "input"))
      (node (ref "IC34") (pin "4") (pinfunction "D0_4") (pintype "input"))
      (node (ref "IC34") (pin "6") (pinfunction "POL_6") (pintype "input"))
      (node (ref "IC34") (pin "7") (pinfunction "D1_7") (pintype "input"))
    )
    (net (code "77") (name "Net-(IC34A-Q0)") (class "Default")
      (node (ref "IC34") (pin "1") (pinfunction "Q3_1") (pintype "output"))
      (node (ref "IC34") (pin "10") (pinfunction "Q1_10") (pintype "output"))
      (node (ref "IC34") (pin "11") (pinfunction "Q2_11") (pintype "output"))
      (node (ref "IC34") (pin "2") (pinfunction "Q0_2") (pintype "output"))
      (node (ref "IC35") (pin "1") (pinfunction "I0_1") (pintype "input"))
    )
    (net (code "78") (name "Net-(IC34A-~{Q0})") (class "Default")
      (node (ref "IC34") (pin "12") (pinfunction "~{Q2}_12") (pintype "output"))
      (node (ref "IC34") (pin "15") (pinfunction "~{Q3}_15") (pintype "output"))
      (node (ref "IC34") (pin "3") (pinfunction "~{Q0}_3") (pintype "output"))
      (node (ref "IC34") (pin "9") (pinfunction "~{Q1}_9") (pintype "output"))
      (node (ref "IC36") (pin "13") (pinfunction "D2_13") (pintype "input"))
      (node (ref "IC36") (pin "14") (pinfunction "D3_14") (pintype "input"))
      (node (ref "IC36") (pin "4") (pinfunction "D0_4") (pintype "input"))
      (node (ref "IC36") (pin "6") (pinfunction "POL_6") (pintype "input"))
      (node (ref "IC36") (pin "7") (pinfunction "D1_7") (pintype "input"))
    )
    (net (code "79") (name "Net-(IC35A-I1)") (class "Default")
      (node (ref "IC35") (pin "2") (pinfunction "I1_2") (pintype "input"))
      (node (ref "IC36") (pin "1") (pinfunction "Q3_1") (pintype "output"))
      (node (ref "IC36") (pin "10") (pinfunction "Q1_10") (pintype "output"))
      (node (ref "IC36") (pin "11") (pinfunction "Q2_11") (pintype "output"))
      (node (ref "IC36") (pin "2") (pinfunction "Q0_2") (pintype "output"))
    )
    (net (code "80") (name "Net-(IC37A-D0)") (class "Default")
      (node (ref "C11") (pin "1") (pinfunction "1_1") (pintype "passive"))
      (node (ref "IC37") (pin "13") (pinfunction "D2_13") (pintype "input"))
      (node (ref "IC37") (pin "14") (pinfunction "D3_14") (pintype "input"))
      (node (ref "IC37") (pin "4") (pinfunction "D0_4") (pintype "input"))
      (node (ref "IC37") (pin "6") (pinfunction "POL_6") (pintype "input"))
      (node (ref "IC37") (pin "7") (pinfunction "D1_7") (pintype "input"))
      (node (ref "R19") (pin "2") (pinfunction "2_2") (pintype "passive"))
      (node (ref "R20") (pin "2") (pinfunction "2_2") (pintype "passive"))
    )
    (net (code "81") (name "Net-(IC37A-Q0)") (class "Default")
      (node (ref "IC37") (pin "1") (pinfunction "Q3_1") (pintype "output"))
      (node (ref "IC37") (pin "10") (pinfunction "Q1_10") (pintype "output"))
      (node (ref "IC37") (pin "11") (pinfunction "Q2_11") (pintype "output"))
      (node (ref "IC37") (pin "2") (pinfunction "Q0_2") (pintype "output"))
      (node (ref "IC38") (pin "13") (pinfunction "D2_13") (pintype "input"))
      (node (ref "IC38") (pin "14") (pinfunction "D3_14") (pintype "input"))
      (node (ref "IC38") (pin "4") (pinfunction "D0_4") (pintype "input"))
      (node (ref "IC38") (pin "6") (pinfunction "POL_6") (pintype "input"))
      (node (ref "IC38") (pin "7") (pinfunction "D1_7") (pintype "input"))
    )
    (net (code "82") (name "Net-(IC38A-Q0)") (class "Default")
      (node (ref "IC38") (pin "1") (pinfunction "Q3_1") (pintype "output"))
      (node (ref "IC38") (pin "10") (pinfunction "Q1_10") (pintype "output"))
      (node (ref "IC38") (pin "11") (pinfunction "Q2_11") (pintype "output"))
      (node (ref "IC38") (pin "2") (pinfunction "Q0_2") (pintype "output"))
      (node (ref "IC39") (pin "1") (pinfunction "I0_1") (pintype "input"))
    )
    (net (code "83") (name "Net-(IC38A-~{Q0})") (class "Default")
      (node (ref "IC38") (pin "12") (pinfunction "~{Q2}_12") (pintype "output"))
      (node (ref "IC38") (pin "15") (pinfunction "~{Q3}_15") (pintype "output"))
      (node (ref "IC38") (pin "3") (pinfunction "~{Q0}_3") (pintype "output"))
      (node (ref "IC38") (pin "9") (pinfunction "~{Q1}_9") (pintype "output"))
      (node (ref "IC40") (pin "13") (pinfunction "D2_13") (pintype "input"))
      (node (ref "IC40") (pin "14") (pinfunction "D3_14") (pintype "input"))
      (node (ref "IC40") (pin "4") (pinfunction "D0_4") (pintype "input"))
      (node (ref "IC40") (pin "6") (pinfunction "POL_6") (pintype "input"))
      (node (ref "IC40") (pin "7") (pinfunction "D1_7") (pintype "input"))
    )
    (net (code "84") (name "Net-(IC39A-I1)") (class "Default")
      (node (ref "IC39") (pin "2") (pinfunction "I1_2") (pintype "input"))
      (node (ref "IC40") (pin "1") (pinfunction "Q3_1") (pintype "output"))
      (node (ref "IC40") (pin "10") (pinfunction "Q1_10") (pintype "output"))
      (node (ref "IC40") (pin "11") (pinfunction "Q2_11") (pintype "output"))
      (node (ref "IC40") (pin "2") (pinfunction "Q0_2") (pintype "output"))
    )
    (net (code "85") (name "Net-(IC41A-D0)") (class "Default")
      (node (ref "C12") (pin "1") (pinfunction "1_1") (pintype "passive"))
      (node (ref "IC41") (pin "13") (pinfunction "D2_13") (pintype "input"))
      (node (ref "IC41") (pin "14") (pinfunction "D3_14") (pintype "input"))
      (node (ref "IC41") (pin "4") (pinfunction "D0_4") (pintype "input"))
      (node (ref "IC41") (pin "6") (pinfunction "POL_6") (pintype "input"))
      (node (ref "IC41") (pin "7") (pinfunction "D1_7") (pintype "input"))
      (node (ref "R21") (pin "2") (pinfunction "2_2") (pintype "passive"))
      (node (ref "R22") (pin "2") (pinfunction "2_2") (pintype "passive"))
    )
    (net (code "86") (name "Net-(IC41A-Q0)") (class "Default")
      (node (ref "IC41") (pin "1") (pinfunction "Q3_1") (pintype "output"))
      (node (ref "IC41") (pin "10") (pinfunction "Q1_10") (pintype "output"))
      (node (ref "IC41") (pin "11") (pinfunction "Q2_11") (pintype "output"))
      (node (ref "IC41") (pin "2") (pinfunction "Q0_2") (pintype "output"))
      (node (ref "IC42") (pin "13") (pinfunction "D2_13") (pintype "input"))
      (node (ref "IC42") (pin "14") (pinfunction "D3_14") (pintype "input"))
      (node (ref "IC42") (pin "4") (pinfunction "D0_4") (pintype "input"))
      (node (ref "IC42") (pin "6") (pinfunction "POL_6") (pintype "input"))
      (node (ref "IC42") (pin "7") (pinfunction "D1_7") (pintype "input"))
    )
    (net (code "87") (name "Net-(IC42A-Q0)") (class "Default")
      (node (ref "IC42") (pin "1") (pinfunction "Q3_1") (pintype "output"))
      (node (ref "IC42") (pin "10") (pinfunction "Q1_10") (pintype "output"))
      (node (ref "IC42") (pin "11") (pinfunction "Q2_11") (pintype "output"))
      (node (ref "IC42") (pin "2") (pinfunction "Q0_2") (pintype "output"))
      (node (ref "IC43") (pin "1") (pinfunction "I0_1") (pintype "input"))
    )
    (net (code "88") (name "Net-(IC42A-~{Q0})") (class "Default")
      (node (ref "IC42") (pin "12") (pinfunction "~{Q2}_12") (pintype "output"))
      (node (ref "IC42") (pin "15") (pinfunction "~{Q3}_15") (pintype "output"))
      (node (ref "IC42") (pin "3") (pinfunction "~{Q0}_3") (pintype "output"))
      (node (ref "IC42") (pin "9") (pinfunction "~{Q1}_9") (pintype "output"))
      (node (ref "IC44") (pin "13") (pinfunction "D2_13") (pintype "input"))
      (node (ref "IC44") (pin "14") (pinfunction "D3_14") (pintype "input"))
      (node (ref "IC44") (pin "4") (pinfunction "D0_4") (pintype "input"))
      (node (ref "IC44") (pin "6") (pinfunction "POL_6") (pintype "input"))
      (node (ref "IC44") (pin "7") (pinfunction "D1_7") (pintype "input"))
    )
    (net (code "89") (name "Net-(IC43A-I1)") (class "Default")
      (node (ref "IC43") (pin "2") (pinfunction "I1_2") (pintype "input"))
      (node (ref "IC44") (pin "1") (pinfunction "Q3_1") (pintype "output"))
      (node (ref "IC44") (pin "10") (pinfunction "Q1_10") (pintype "output"))
      (node (ref "IC44") (pin "11") (pinfunction "Q2_11") (pintype "output"))
      (node (ref "IC44") (pin "2") (pinfunction "Q0_2") (pintype "output"))
    )
    (net (code "90") (name "Net-(IC45A-D0)") (class "Default")
      (node (ref "C13") (pin "1") (pinfunction "1_1") (pintype "passive"))
      (node (ref "IC45") (pin "13") (pinfunction "D2_13") (pintype "input"))
      (node (ref "IC45") (pin "14") (pinfunction "D3_14") (pintype "input"))
      (node (ref "IC45") (pin "4") (pinfunction "D0_4") (pintype "input"))
      (node (ref "IC45") (pin "6") (pinfunction "POL_6") (pintype "input"))
      (node (ref "IC45") (pin "7") (pinfunction "D1_7") (pintype "input"))
      (node (ref "R23") (pin "2") (pinfunction "2_2") (pintype "passive"))
      (node (ref "R24") (pin "2") (pinfunction "2_2") (pintype "passive"))
    )
    (net (code "91") (name "Net-(IC45A-Q0)") (class "Default")
      (node (ref "IC45") (pin "1") (pinfunction "Q3_1") (pintype "output"))
      (node (ref "IC45") (pin "10") (pinfunction "Q1_10") (pintype "output"))
      (node (ref "IC45") (pin "11") (pinfunction "Q2_11") (pintype "output"))
      (node (ref "IC45") (pin "2") (pinfunction "Q0_2") (pintype "output"))
      (node (ref "IC46") (pin "13") (pinfunction "D2_13") (pintype "input"))
      (node (ref "IC46") (pin "14") (pinfunction "D3_14") (pintype "input"))
      (node (ref "IC46") (pin "4") (pinfunction "D0_4") (pintype "input"))
      (node (ref "IC46") (pin "6") (pinfunction "POL_6") (pintype "input"))
      (node (ref "IC46") (pin "7") (pinfunction "D1_7") (pintype "input"))
    )
    (net (code "92") (name "Net-(IC46A-Q0)") (class "Default")
      (node (ref "IC46") (pin "1") (pinfunction "Q3_1") (pintype "output"))
      (node (ref "IC46") (pin "10") (pinfunction "Q1_10") (pintype "output"))
      (node (ref "IC46") (pin "11") (pinfunction "Q2_11") (pintype "output"))
      (node (ref "IC46") (pin "2") (pinfunction "Q0_2") (pintype "output"))
      (node (ref "IC47") (pin "1") (pinfunction "I0_1") (pintype "input"))
    )
    (net (code "93") (name "Net-(IC46A-~{Q0})") (class "Default")
      (node (ref "IC46") (pin "12") (pinfunction "~{Q2}_12") (pintype "output"))
      (node (ref "IC46") (pin "15") (pinfunction "~{Q3}_15") (pintype "output"))
      (node (ref "IC46") (pin "3") (pinfunction "~{Q0}_3") (pintype "output"))
      (node (ref "IC46") (pin "9") (pinfunction "~{Q1}_9") (pintype "output"))
      (node (ref "IC48") (pin "13") (pinfunction "D2_13") (pintype "input"))
      (node (ref "IC48") (pin "14") (pinfunction "D3_14") (pintype "input"))
      (node (ref "IC48") (pin "4") (pinfunction "D0_4") (pintype "input"))
      (node (ref "IC48") (pin "6") (pinfunction "POL_6") (pintype "input"))
      (node (ref "IC48") (pin "7") (pinfunction "D1_7") (pintype "input"))
    )
    (net (code "94") (name "Net-(IC47A-I1)") (class "Default")
      (node (ref "IC47") (pin "2") (pinfunction "I1_2") (pintype "input"))
      (node (ref "IC48") (pin "1") (pinfunction "Q3_1") (pintype "output"))
      (node (ref "IC48") (pin "10") (pinfunction "Q1_10") (pintype "output"))
      (node (ref "IC48") (pin "11") (pinfunction "Q2_11") (pintype "output"))
      (node (ref "IC48") (pin "2") (pinfunction "Q0_2") (pintype "output"))
    )
    (net (code "95") (name "Net-(IC49A-D0)") (class "Default")
      (node (ref "C14") (pin "1") (pinfunction "1_1") (pintype "passive"))
      (node (ref "IC49") (pin "13") (pinfunction "D2_13") (pintype "input"))
      (node (ref "IC49") (pin "14") (pinfunction "D3_14") (pintype "input"))
      (node (ref "IC49") (pin "4") (pinfunction "D0_4") (pintype "input"))
      (node (ref "IC49") (pin "6") (pinfunction "POL_6") (pintype "input"))
      (node (ref "IC49") (pin "7") (pinfunction "D1_7") (pintype "input"))
      (node (ref "R25") (pin "2") (pinfunction "2_2") (pintype "passive"))
      (node (ref "R26") (pin "2") (pinfunction "2_2") (pintype "passive"))
    )
    (net (code "96") (name "Net-(IC49A-Q0)") (class "Default")
      (node (ref "IC49") (pin "1") (pinfunction "Q3_1") (pintype "output"))
      (node (ref "IC49") (pin "10") (pinfunction "Q1_10") (pintype "output"))
      (node (ref "IC49") (pin "11") (pinfunction "Q2_11") (pintype "output"))
      (node (ref "IC49") (pin "2") (pinfunction "Q0_2") (pintype "output"))
      (node (ref "IC50") (pin "13") (pinfunction "D2_13") (pintype "input"))
      (node (ref "IC50") (pin "14") (pinfunction "D3_14") (pintype "input"))
      (node (ref "IC50") (pin "4") (pinfunction "D0_4") (pintype "input"))
      (node (ref "IC50") (pin "6") (pinfunction "POL_6") (pintype "input"))
      (node (ref "IC50") (pin "7") (pinfunction "D1_7") (pintype "input"))
    )
    (net (code "97") (name "Net-(IC50A-Q0)") (class "Default")
      (node (ref "IC50") (pin "1") (pinfunction "Q3_1") (pintype "output"))
      (node (ref "IC50") (pin "10") (pinfunction "Q1_10") (pintype "output"))
      (node (ref "IC50") (pin "11") (pinfunction "Q2_11") (pintype "output"))
      (node (ref "IC50") (pin "2") (pinfunction "Q0_2") (pintype "output"))
      (node (ref "IC51") (pin "1") (pinfunction "I0_1") (pintype "input"))
    )
    (net (code "98") (name "Net-(IC50A-~{Q0})") (class "Default")
      (node (ref "IC50") (pin "12") (pinfunction "~{Q2}_12") (pintype "output"))
      (node (ref "IC50") (pin "15") (pinfunction "~{Q3}_15") (pintype "output"))
      (node (ref "IC50") (pin "3") (pinfunction "~{Q0}_3") (pintype "output"))
      (node (ref "IC50") (pin "9") (pinfunction "~{Q1}_9") (pintype "output"))
      (node (ref "IC52") (pin "13") (pinfunction "D2_13") (pintype "input"))
      (node (ref "IC52") (pin "14") (pinfunction "D3_14") (pintype "input"))
      (node (ref "IC52") (pin "4") (pinfunction "D0_4") (pintype "input"))
      (node (ref "IC52") (pin "6") (pinfunction "POL_6") (pintype "input"))
      (node (ref "IC52") (pin "7") (pinfunction "D1_7") (pintype "input"))
    )
    (net (code "99") (name "Net-(IC51A-I1)") (class "Default")
      (node (ref "IC51") (pin "2") (pinfunction "I1_2") (pintype "input"))
      (node (ref "IC52") (pin "1") (pinfunction "Q3_1") (pintype "output"))
      (node (ref "IC52") (pin "10") (pinfunction "Q1_10") (pintype "output"))
      (node (ref "IC52") (pin "11") (pinfunction "Q2_11") (pintype "output"))
      (node (ref "IC52") (pin "2") (pinfunction "Q0_2") (pintype "output"))
    )
    (net (code "100") (name "Net-(IC53A-D0)") (class "Default")
      (node (ref "C15") (pin "1") (pinfunction "1_1") (pintype "passive"))
      (node (ref "IC53") (pin "13") (pinfunction "D2_13") (pintype "input"))
      (node (ref "IC53") (pin "14") (pinfunction "D3_14") (pintype "input"))
      (node (ref "IC53") (pin "4") (pinfunction "D0_4") (pintype "input"))
      (node (ref "IC53") (pin "6") (pinfunction "POL_6") (pintype "input"))
      (node (ref "IC53") (pin "7") (pinfunction "D1_7") (pintype "input"))
      (node (ref "R27") (pin "2") (pinfunction "2_2") (pintype "passive"))
      (node (ref "R28") (pin "2") (pinfunction "2_2") (pintype "passive"))
    )
    (net (code "101") (name "Net-(IC53A-Q0)") (class "Default")
      (node (ref "IC53") (pin "1") (pinfunction "Q3_1") (pintype "output"))
      (node (ref "IC53") (pin "10") (pinfunction "Q1_10") (pintype "output"))
      (node (ref "IC53") (pin "11") (pinfunction "Q2_11") (pintype "output"))
      (node (ref "IC53") (pin "2") (pinfunction "Q0_2") (pintype "output"))
      (node (ref "IC54") (pin "13") (pinfunction "D2_13") (pintype "input"))
      (node (ref "IC54") (pin "14") (pinfunction "D3_14") (pintype "input"))
      (node (ref "IC54") (pin "4") (pinfunction "D0_4") (pintype "input"))
      (node (ref "IC54") (pin "6") (pinfunction "POL_6") (pintype "input"))
      (node (ref "IC54") (pin "7") (pinfunction "D1_7") (pintype "input"))
    )
    (net (code "102") (name "Net-(IC54A-Q0)") (class "Default")
      (node (ref "IC54") (pin "1") (pinfunction "Q3_1") (pintype "output"))
      (node (ref "IC54") (pin "10") (pinfunction "Q1_10") (pintype "output"))
      (node (ref "IC54") (pin "11") (pinfunction "Q2_11") (pintype "output"))
      (node (ref "IC54") (pin "2") (pinfunction "Q0_2") (pintype "output"))
      (node (ref "IC55") (pin "1") (pinfunction "I0_1") (pintype "input"))
    )
    (net (code "103") (name "Net-(IC54A-~{Q0})") (class "Default")
      (node (ref "IC54") (pin "12") (pinfunction "~{Q2}_12") (pintype "output"))
      (node (ref "IC54") (pin "15") (pinfunction "~{Q3}_15") (pintype "output"))
      (node (ref "IC54") (pin "3") (pinfunction "~{Q0}_3") (pintype "output"))
      (node (ref "IC54") (pin "9") (pinfunction "~{Q1}_9") (pintype "output"))
      (node (ref "IC56") (pin "13") (pinfunction "D2_13") (pintype "input"))
      (node (ref "IC56") (pin "14") (pinfunction "D3_14") (pintype "input"))
      (node (ref "IC56") (pin "4") (pinfunction "D0_4") (pintype "input"))
      (node (ref "IC56") (pin "6") (pinfunction "POL_6") (pintype "input"))
      (node (ref "IC56") (pin "7") (pinfunction "D1_7") (pintype "input"))
    )
    (net (code "104") (name "Net-(IC55A-I1)") (class "Default")
      (node (ref "IC55") (pin "2") (pinfunction "I1_2") (pintype "input"))
      (node (ref "IC56") (pin "1") (pinfunction "Q3_1") (pintype "output"))
      (node (ref "IC56") (pin "10") (pinfunction "Q1_10") (pintype "output"))
      (node (ref "IC56") (pin "11") (pinfunction "Q2_11") (pintype "output"))
      (node (ref "IC56") (pin "2") (pinfunction "Q0_2") (pintype "output"))
    )
    (net (code "105") (name "Net-(IC57A-D0)") (class "Default")
      (node (ref "C16") (pin "1") (pinfunction "1_1") (pintype "passive"))
      (node (ref "IC57") (pin "13") (pinfunction "D2_13") (pintype "input"))
      (node (ref "IC57") (pin "14") (pinfunction "D3_14") (pintype "input"))
      (node (ref "IC57") (pin "4") (pinfunction "D0_4") (pintype "input"))
      (node (ref "IC57") (pin "6") (pinfunction "POL_6") (pintype "input"))
      (node (ref "IC57") (pin "7") (pinfunction "D1_7") (pintype "input"))
      (node (ref "R29") (pin "2") (pinfunction "2_2") (pintype "passive"))
      (node (ref "R30") (pin "2") (pinfunction "2_2") (pintype "passive"))
    )
    (net (code "106") (name "Net-(IC57A-Q0)") (class "Default")
      (node (ref "IC57") (pin "1") (pinfunction "Q3_1") (pintype "output"))
      (node (ref "IC57") (pin "10") (pinfunction "Q1_10") (pintype "output"))
      (node (ref "IC57") (pin "11") (pinfunction "Q2_11") (pintype "output"))
      (node (ref "IC57") (pin "2") (pinfunction "Q0_2") (pintype "output"))
      (node (ref "IC58") (pin "13") (pinfunction "D2_13") (pintype "input"))
      (node (ref "IC58") (pin "14") (pinfunction "D3_14") (pintype "input"))
      (node (ref "IC58") (pin "4") (pinfunction "D0_4") (pintype "input"))
      (node (ref "IC58") (pin "6") (pinfunction "POL_6") (pintype "input"))
      (node (ref "IC58") (pin "7") (pinfunction "D1_7") (pintype "input"))
    )
    (net (code "107") (name "Net-(IC58A-Q0)") (class "Default")
      (node (ref "IC58") (pin "1") (pinfunction "Q3_1") (pintype "output"))
      (node (ref "IC58") (pin "10") (pinfunction "Q1_10") (pintype "output"))
      (node (ref "IC58") (pin "11") (pinfunction "Q2_11") (pintype "output"))
      (node (ref "IC58") (pin "2") (pinfunction "Q0_2") (pintype "output"))
      (node (ref "IC59") (pin "1") (pinfunction "I0_1") (pintype "input"))
    )
    (net (code "108") (name "Net-(IC58A-~{Q0})") (class "Default")
      (node (ref "IC58") (pin "12") (pinfunction "~{Q2}_12") (pintype "output"))
      (node (ref "IC58") (pin "15") (pinfunction "~{Q3}_15") (pintype "output"))
      (node (ref "IC58") (pin "3") (pinfunction "~{Q0}_3") (pintype "output"))
      (node (ref "IC58") (pin "9") (pinfunction "~{Q1}_9") (pintype "output"))
      (node (ref "IC60") (pin "13") (pinfunction "D2_13") (pintype "input"))
      (node (ref "IC60") (pin "14") (pinfunction "D3_14") (pintype "input"))
      (node (ref "IC60") (pin "4") (pinfunction "D0_4") (pintype "input"))
      (node (ref "IC60") (pin "6") (pinfunction "POL_6") (pintype "input"))
      (node (ref "IC60") (pin "7") (pinfunction "D1_7") (pintype "input"))
    )
    (net (code "109") (name "Net-(IC59A-I1)") (class "Default")
      (node (ref "IC59") (pin "2") (pinfunction "I1_2") (pintype "input"))
      (node (ref "IC60") (pin "1") (pinfunction "Q3_1") (pintype "output"))
      (node (ref "IC60") (pin "10") (pinfunction "Q1_10") (pintype "output"))
      (node (ref "IC60") (pin "11") (pinfunction "Q2_11") (pintype "output"))
      (node (ref "IC60") (pin "2") (pinfunction "Q0_2") (pintype "output"))
    )
    (net (code "110") (name "Net-(IC61A-D0)") (class "Default")
      (node (ref "C17") (pin "1") (pinfunction "1_1") (pintype "passive"))
      (node (ref "IC61") (pin "13") (pinfunction "D2_13") (pintype "input"))
      (node (ref "IC61") (pin "14") (pinfunction "D3_14") (pintype "input"))
      (node (ref "IC61") (pin "4") (pinfunction "D0_4") (pintype "input"))
      (node (ref "IC61") (pin "6") (pinfunction "POL_6") (pintype "input"))
      (node (ref "IC61") (pin "7") (pinfunction "D1_7") (pintype "input"))
      (node (ref "R31") (pin "2") (pinfunction "2_2") (pintype "passive"))
      (node (ref "R32") (pin "2") (pinfunction "2_2") (pintype "passive"))
    )
    (net (code "111") (name "Net-(IC61A-Q0)") (class "Default")
      (node (ref "IC61") (pin "1") (pinfunction "Q3_1") (pintype "output"))
      (node (ref "IC61") (pin "10") (pinfunction "Q1_10") (pintype "output"))
      (node (ref "IC61") (pin "11") (pinfunction "Q2_11") (pintype "output"))
      (node (ref "IC61") (pin "2") (pinfunction "Q0_2") (pintype "output"))
      (node (ref "IC62") (pin "13") (pinfunction "D2_13") (pintype "input"))
      (node (ref "IC62") (pin "14") (pinfunction "D3_14") (pintype "input"))
      (node (ref "IC62") (pin "4") (pinfunction "D0_4") (pintype "input"))
      (node (ref "IC62") (pin "6") (pinfunction "POL_6") (pintype "input"))
      (node (ref "IC62") (pin "7") (pinfunction "D1_7") (pintype "input"))
    )
    (net (code "112") (name "Net-(IC62A-Q0)") (class "Default")
      (node (ref "IC62") (pin "1") (pinfunction "Q3_1") (pintype "output"))
      (node (ref "IC62") (pin "10") (pinfunction "Q1_10") (pintype "output"))
      (node (ref "IC62") (pin "11") (pinfunction "Q2_11") (pintype "output"))
      (node (ref "IC62") (pin "2") (pinfunction "Q0_2") (pintype "output"))
      (node (ref "IC63") (pin "1") (pinfunction "I0_1") (pintype "input"))
    )
    (net (code "113") (name "Net-(IC62A-~{Q0})") (class "Default")
      (node (ref "IC62") (pin "12") (pinfunction "~{Q2}_12") (pintype "output"))
      (node (ref "IC62") (pin "15") (pinfunction "~{Q3}_15") (pintype "output"))
      (node (ref "IC62") (pin "3") (pinfunction "~{Q0}_3") (pintype "output"))
      (node (ref "IC62") (pin "9") (pinfunction "~{Q1}_9") (pintype "output"))
      (node (ref "IC64") (pin "13") (pinfunction "D2_13") (pintype "input"))
      (node (ref "IC64") (pin "14") (pinfunction "D3_14") (pintype "input"))
      (node (ref "IC64") (pin "4") (pinfunction "D0_4") (pintype "input"))
      (node (ref "IC64") (pin "6") (pinfunction "POL_6") (pintype "input"))
      (node (ref "IC64") (pin "7") (pinfunction "D1_7") (pintype "input"))
    )
    (net (code "114") (name "Net-(IC63A-I1)") (class "Default")
      (node (ref "IC63") (pin "2") (pinfunction "I1_2") (pintype "input"))
      (node (ref "IC64") (pin "1") (pinfunction "Q3_1") (pintype "output"))
      (node (ref "IC64") (pin "10") (pinfunction "Q1_10") (pintype "output"))
      (node (ref "IC64") (pin "11") (pinfunction "Q2_11") (pintype "output"))
      (node (ref "IC64") (pin "2") (pinfunction "Q0_2") (pintype "output"))
    )
    (net (code "115") (name "Net-(KICK_DRUM-Pad1)") (class "Default")
      (node (ref "KICK_DRUM") (pin "1") (pinfunction "1_1") (pintype "passive"))
      (node (ref "KNOB_CONNECTIONS") (pin "2") (pinfunction "2_2") (pintype "passive"))
      (node (ref "KNOB_CONNECTIONS") (pin "4") (pinfunction "4_4") (pintype "passive"))
      (node (ref "KNOB_CONNECTIONS") (pin "6") (pinfunction "6_6") (pintype "passive"))
      (node (ref "PIN_CONNECTIONS") (pin "2") (pinfunction "2_2") (pintype "passive"))
    )
    (net (code "116") (name "Net-(KICK_DRUM-Pad2)") (class "Default")
      (node (ref "KICK_DRUM") (pin "2") (pinfunction "2_2") (pintype "passive"))
      (node (ref "KICK_DRUM") (pin "4") (pinfunction "4_4") (pintype "passive"))
      (node (ref "MIXER") (pin "1") (pinfunction "1_1") (pintype "passive"))
    )
    (net (code "117") (name "Net-(KNOB_CONNECTIONS-Pad14)") (class "Default")
      (node (ref "KNOB_CONNECTIONS") (pin "14") (pinfunction "14_14") (pintype "passive"))
      (node (ref "KNOB_CONNECTIONS") (pin "16") (pinfunction "16_16") (pintype "passive"))
      (node (ref "KNOB_CONNECTIONS") (pin "18") (pinfunction "18_18") (pintype "passive"))
      (node (ref "LO_TOM") (pin "1") (pinfunction "1_1") (pintype "passive"))
      (node (ref "PIN_CONNECTIONS") (pin "6") (pinfunction "6_6") (pintype "passive"))
    )
    (net (code "118") (name "Net-(KNOB_CONNECTIONS-Pad20)") (class "Default")
      (node (ref "KNOB_CONNECTIONS") (pin "20") (pinfunction "20_20") (pintype "passive"))
      (node (ref "KNOB_CONNECTIONS") (pin "22") (pinfunction "22_22") (pintype "passive"))
      (node (ref "KNOB_CONNECTIONS") (pin "24") (pinfunction "24_24") (pintype "passive"))
      (node (ref "PIN_CONNECTIONS") (pin "8") (pinfunction "8_8") (pintype "passive"))
      (node (ref "SNARE_DRUM") (pin "1") (pinfunction "1_1") (pintype "passive"))
    )
    (net (code "119") (name "Net-(KNOB_CONNECTIONS-Pad44)") (class "Default")
      (node (ref "KNOB_CONNECTIONS") (pin "44") (pinfunction "44_44") (pintype "passive"))
      (node (ref "KNOB_CONNECTIONS") (pin "46") (pinfunction "46_46") (pintype "passive"))
      (node (ref "KNOB_CONNECTIONS") (pin "48") (pinfunction "48_48") (pintype "passive"))
      (node (ref "PIN_CONNECTIONS") (pin "16") (pinfunction "16_16") (pintype "passive"))
      (node (ref "SPECIAL_INSTRUMENT") (pin "1") (pinfunction "1_1") (pintype "passive"))
    )
    (net (code "120") (name "Net-(LO_TOM-Pad2)") (class "Default")
      (node (ref "LO_TOM") (pin "2") (pinfunction "2_2") (pintype "passive"))
      (node (ref "LO_TOM") (pin "4") (pinfunction "4_4") (pintype "passive"))
      (node (ref "MIXER") (pin "3") (pinfunction "3_3") (pintype "passive"))
    )
    (net (code "121") (name "Net-(MIXER-Pad4)") (class "Default")
      (node (ref "MIXER") (pin "4") (pinfunction "4_4") (pintype "passive"))
      (node (ref "SNARE_DRUM") (pin "2") (pinfunction "2_2") (pintype "passive"))
      (node (ref "SNARE_DRUM") (pin "4") (pinfunction "4_4") (pintype "passive"))
    )
    (net (code "122") (name "Net-(MIXER-Pad8)") (class "Default")
      (node (ref "MIXER") (pin "8") (pinfunction "8_8") (pintype "passive"))
      (node (ref "SPECIAL_INSTRUMENT") (pin "2") (pinfunction "2_2") (pintype "passive"))
      (node (ref "SPECIAL_INSTRUMENT") (pin "4") (pinfunction "4_4") (pintype "passive"))
    )
    (net (code "123") (name "Net-(PIN_CONNECTIONS-Pad1)") (class "Default")
      (node (ref "PIN_CONNECTIONS") (pin "1") (pinfunction "1_1") (pintype "passive"))
      (node (ref "SEQUENCER") (pin "2") (pinfunction "2_2") (pintype "passive"))
    )
    (net (code "124") (name "Net-(PIN_CONNECTIONS-Pad3)") (class "Default")
      (node (ref "PIN_CONNECTIONS") (pin "3") (pinfunction "3_3") (pintype "passive"))
      (node (ref "SEQUENCER") (pin "4") (pinfunction "4_4") (pintype "passive"))
    )
    (net (code "125") (name "Net-(PIN_CONNECTIONS-Pad5)") (class "Default")
      (node (ref "PIN_CONNECTIONS") (pin "5") (pinfunction "5_5") (pintype "passive"))
      (node (ref "SEQUENCER") (pin "6") (pinfunction "6_6") (pintype "passive"))
    )
    (net (code "126") (name "Net-(PIN_CONNECTIONS-Pad7)") (class "Default")
      (node (ref "PIN_CONNECTIONS") (pin "7") (pinfunction "7_7") (pintype "passive"))
      (node (ref "SEQUENCER") (pin "8") (pinfunction "8_8") (pintype "passive"))
    )
    (net (code "127") (name "Net-(PIN_CONNECTIONS-Pad9)") (class "Default")
      (node (ref "PIN_CONNECTIONS") (pin "9") (pinfunction "9_9") (pintype "passive"))
      (node (ref "SEQUENCER") (pin "10") (pinfunction "10_10") (pintype "passive"))
    )
    (net (code "128") (name "Net-(PIN_CONNECTIONS-Pad11)") (class "Default")
      (node (ref "PIN_CONNECTIONS") (pin "11") (pinfunction "11_11") (pintype "passive"))
      (node (ref "SEQUENCER") (pin "12") (pinfunction "12_12") (pintype "passive"))
    )
    (net (code "129") (name "Net-(PIN_CONNECTIONS-Pad13)") (class "Default")
      (node (ref "PIN_CONNECTIONS") (pin "13") (pinfunction "13_13") (pintype "passive"))
      (node (ref "SEQUENCER") (pin "14") (pinfunction "14_14") (pintype "passive"))
    )
    (net (code "130") (name "Net-(PIN_CONNECTIONS-Pad15)") (class "Default")
      (node (ref "PIN_CONNECTIONS") (pin "15") (pinfunction "15_15") (pintype "passive"))
      (node (ref "SEQUENCER") (pin "16") (pinfunction "16_16") (pintype "passive"))
    )
    (net (code "131") (name "OUTPUT") (class "Default")
      (node (ref "IC11") (pin "3") (pinfunction "O_3") (pintype "output"))
      (node (ref "IC15") (pin "3") (pinfunction "O_3") (pintype "output"))
      (node (ref "IC19") (pin "3") (pinfunction "O_3") (pintype "output"))
      (node (ref "IC23") (pin "3") (pinfunction "O_3") (pintype "output"))
      (node (ref "IC27") (pin "3") (pinfunction "O_3") (pintype "output"))
      (node (ref "IC3") (pin "3") (pinfunction "O_3") (pintype "output"))
      (node (ref "IC31") (pin "3") (pinfunction "O_3") (pintype "output"))
      (node (ref "IC35") (pin "3") (pinfunction "O_3") (pintype "output"))
      (node (ref "IC39") (pin "3") (pinfunction "O_3") (pintype "output"))
      (node (ref "IC43") (pin "3") (pinfunction "O_3") (pintype "output"))
      (node (ref "IC47") (pin "3") (pinfunction "O_3") (pintype "output"))
      (node (ref "IC51") (pin "3") (pinfunction "O_3") (pintype "output"))
      (node (ref "IC55") (pin "3") (pinfunction "O_3") (pintype "output"))
      (node (ref "IC59") (pin "3") (pinfunction "O_3") (pintype "output"))
      (node (ref "IC63") (pin "3") (pinfunction "O_3") (pintype "output"))
      (node (ref "IC7") (pin "3") (pinfunction "O_3") (pintype "output"))
    )
    (net (code "132") (name "VCC") (class "Default")
      (node (ref "C1") (pin "1") (pinfunction "1_1") (pintype "passive"))
      (node (ref "PIN_CONNECTIONS") (pin "17") (pinfunction "17_17") (pintype "passive"))
      (node (ref "POWER_SUPPY") (pin "1") (pinfunction "1_1") (pintype "passive"))
    )
    (net (code "133") (name "unconnected-(BUTTON_2-Pad1)") (class "Default")
      (node (ref "BUTTON_2") (pin "1") (pinfunction "1_1") (pintype "passive"))
    )
    (net (code "134") (name "unconnected-(BUTTON_3-Pad1)") (class "Default")
      (node (ref "BUTTON_3") (pin "1") (pinfunction "1_1") (pintype "passive"))
    )
    (net (code "135") (name "unconnected-(BUTTON_4-Pad1)") (class "Default")
      (node (ref "BUTTON_4") (pin "1") (pinfunction "1_1") (pintype "passive"))
    )
    (net (code "136") (name "unconnected-(BUTTON_5-Pad1)") (class "Default")
      (node (ref "BUTTON_5") (pin "1") (pinfunction "1_1") (pintype "passive"))
    )
    (net (code "137") (name "unconnected-(BUTTON_6-Pad1)") (class "Default")
      (node (ref "BUTTON_6") (pin "1") (pinfunction "1_1") (pintype "passive"))
    )
    (net (code "138") (name "unconnected-(BUTTON_7-Pad1)") (class "Default")
      (node (ref "BUTTON_7") (pin "1") (pinfunction "1_1") (pintype "passive"))
    )
    (net (code "139") (name "unconnected-(BUTTON_8-Pad1)") (class "Default")
      (node (ref "BUTTON_8") (pin "1") (pinfunction "1_1") (pintype "passive"))
    )
    (net (code "140") (name "unconnected-(BUTTON_9-Pad1)") (class "Default")
      (node (ref "BUTTON_9") (pin "1") (pinfunction "1_1") (pintype "passive"))
    )
    (net (code "141") (name "unconnected-(BUTTON_10-Pad1)") (class "Default")
      (node (ref "BUTTON_10") (pin "1") (pinfunction "1_1") (pintype "passive"))
    )
    (net (code "142") (name "unconnected-(BUTTON_11-Pad1)") (class "Default")
      (node (ref "BUTTON_11") (pin "1") (pinfunction "1_1") (pintype "passive"))
    )
    (net (code "143") (name "unconnected-(BUTTON_12-Pad1)") (class "Default")
      (node (ref "BUTTON_12") (pin "1") (pinfunction "1_1") (pintype "passive"))
    )
    (net (code "144") (name "unconnected-(BUTTON_13-Pad1)") (class "Default")
      (node (ref "BUTTON_13") (pin "1") (pinfunction "1_1") (pintype "passive"))
    )
    (net (code "145") (name "unconnected-(BUTTON_14-Pad1)") (class "Default")
      (node (ref "BUTTON_14") (pin "1") (pinfunction "1_1") (pintype "passive"))
    )
    (net (code "146") (name "unconnected-(BUTTON_15-Pad1)") (class "Default")
      (node (ref "BUTTON_15") (pin "1") (pinfunction "1_1") (pintype "passive"))
    )
    (net (code "147") (name "unconnected-(BUTTON_16-Pad1)") (class "Default")
      (node (ref "BUTTON_16") (pin "1") (pinfunction "1_1") (pintype "passive"))
    )
    (net (code "148") (name "unconnected-(KNOB_CONNECTIONS-Pad50)") (class "Default")
      (node (ref "KNOB_CONNECTIONS") (pin "50") (pinfunction "50_50") (pintype "passive"))
    )
    (net (code "149") (name "unconnected-(PIN_CONNECTIONS-Pad18)") (class "Default")
      (node (ref "PIN_CONNECTIONS") (pin "18") (pinfunction "18_18") (pintype "passive"))
    )
    (net (code "150") (name "unconnected-(SEQUENCER-Pad18)") (class "Default")
      (node (ref "SEQUENCER") (pin "18") (pinfunction "18_18") (pintype "passive"))
    )
  )
)
